# io-board-b-d.net
KiCad netlist of a schematic drawn in EAGLE
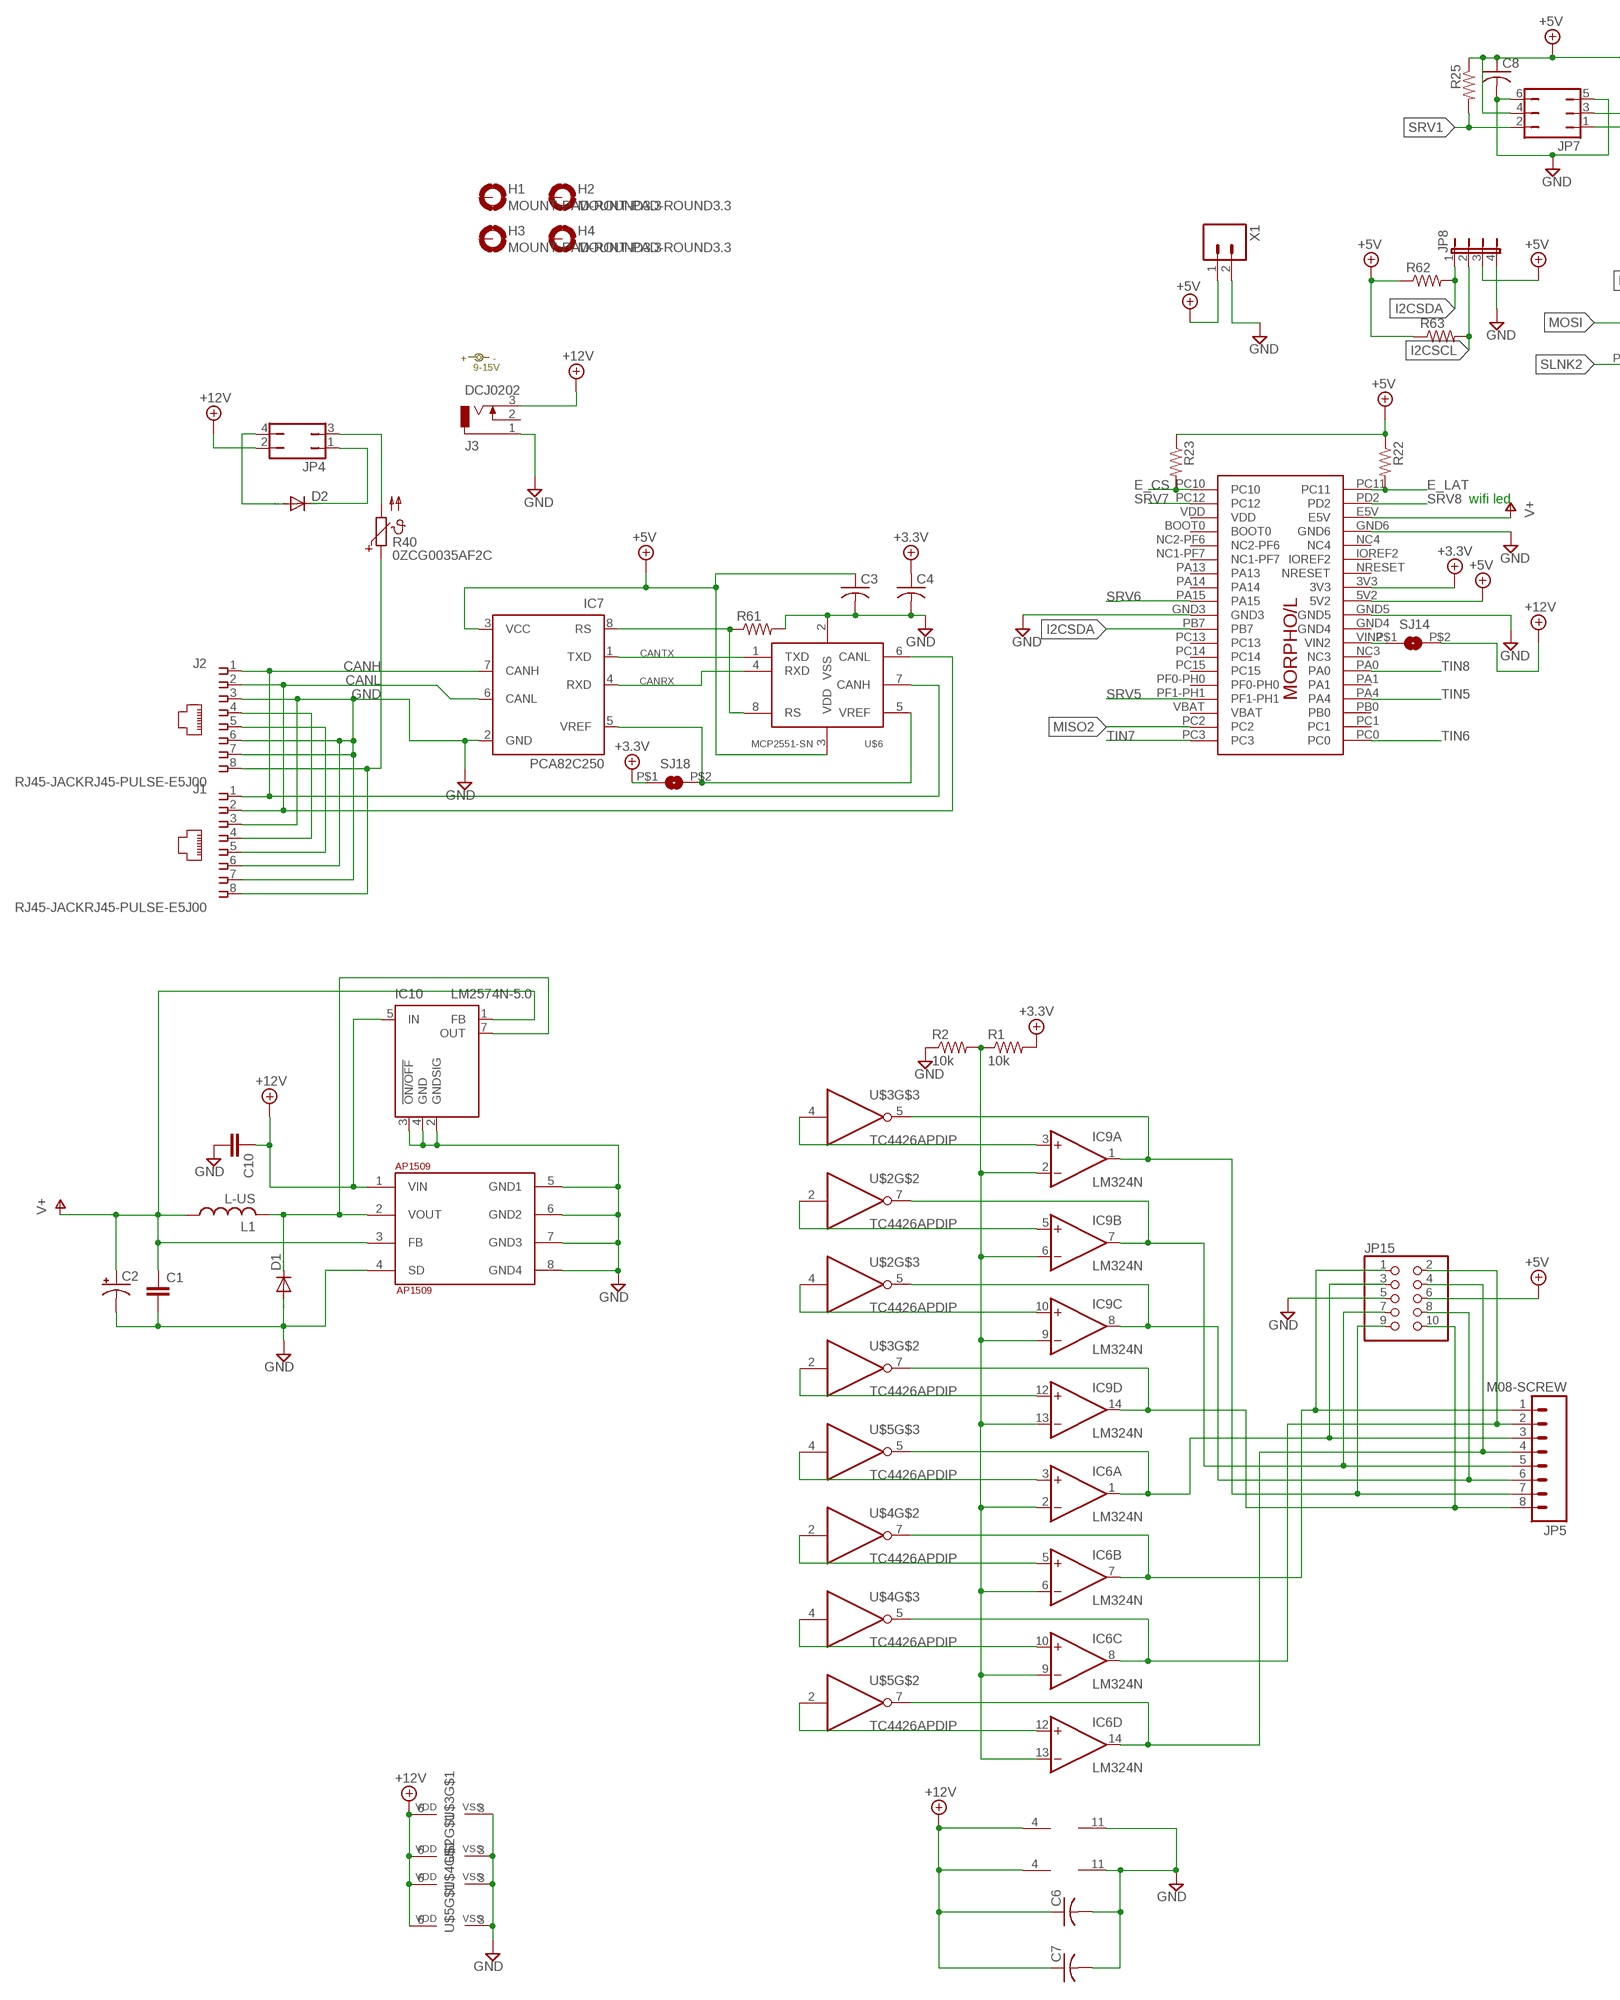
[diagram p0: schematic, sheet 1, part 1 of 2]
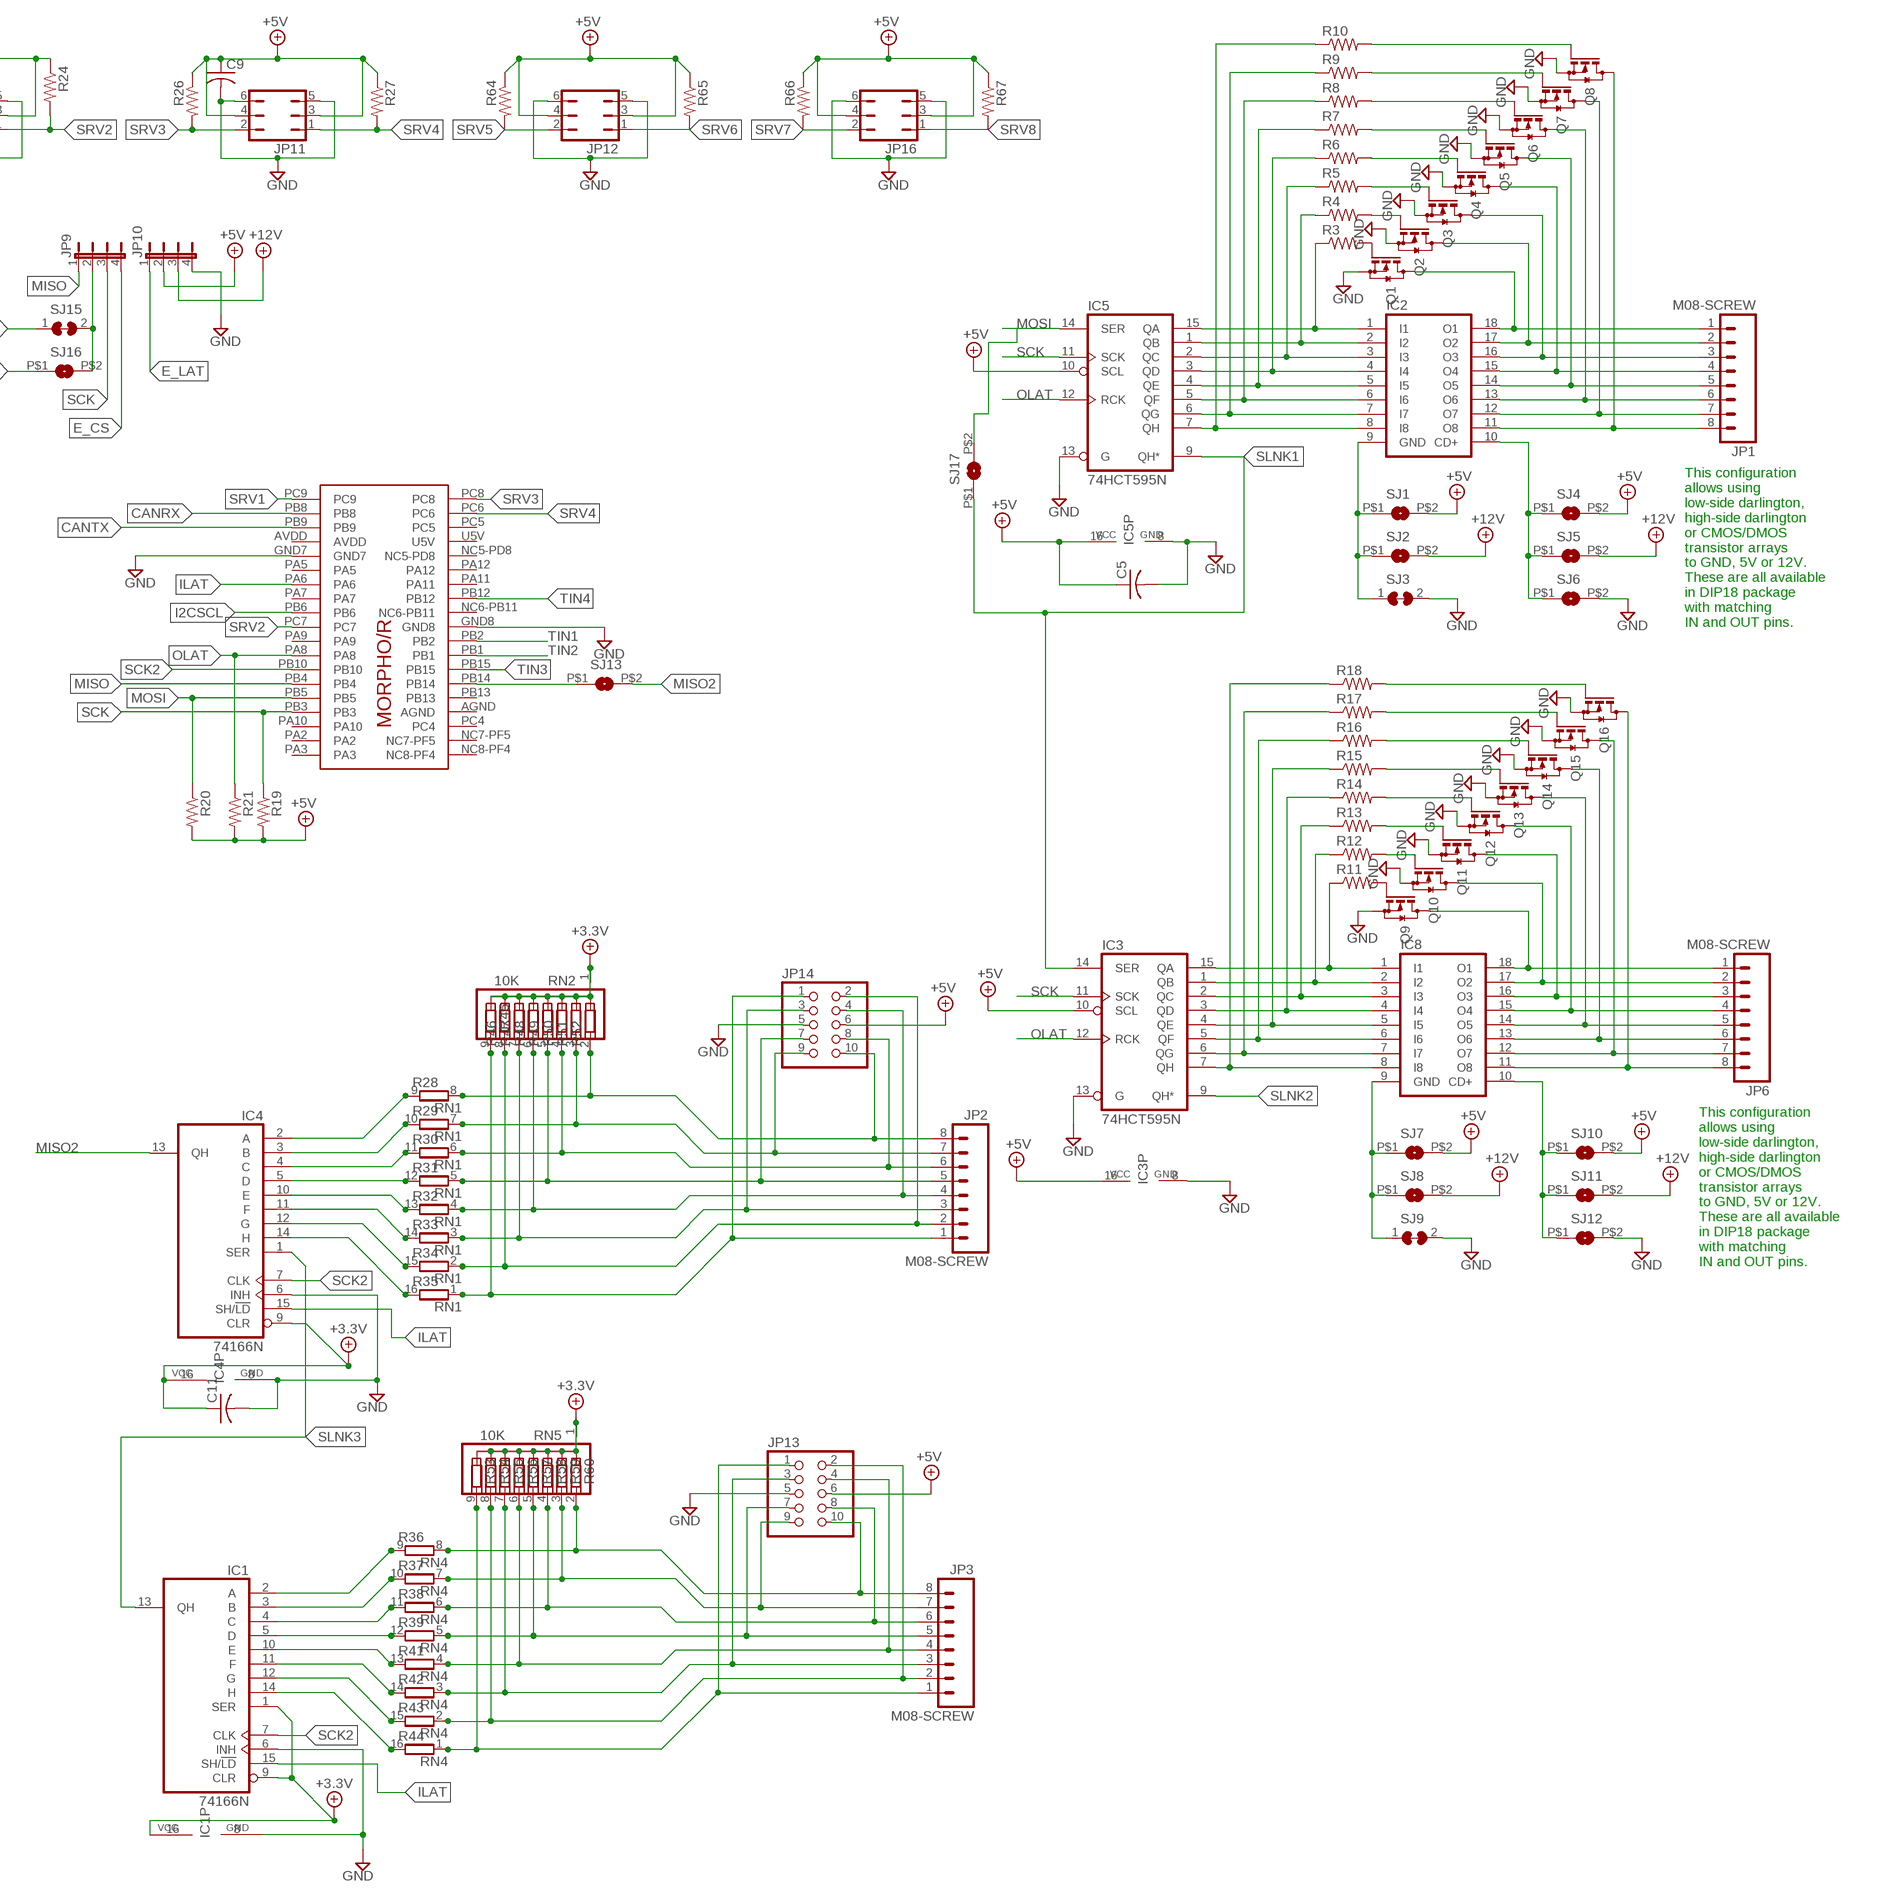
[diagram p1: schematic, sheet 1, part 2 of 2]

(export (version "E")
  (design (tool "Eeschema 10.0.6"))
  (components
    (comp (ref "+12V")
      (value "9-15V")
      (footprint "eagle-import:POWER_USAGE")
      (libsource (lib "eagle-import") (part "DOC-POWER_LABEL"))
    )
    (comp (ref "AP1509")
      (value "AP1509")
      (footprint "eagle-import:SO-08")
      (libsource (lib "eagle-import") (part "AP1509"))
    )
    (comp (ref "C1")
      (value "C-EUC1206")
      (footprint "eagle-import:C1206")
      (libsource (lib "eagle-import") (part "C-EUC1206"))
    )
    (comp (ref "C2")
      (value "CPOL-USE2.5-5")
      (footprint "eagle-import:E2,5-5")
      (libsource (lib "eagle-import") (part "CPOL-USE2.5-5"))
    )
    (comp (ref "C3")
      (value "C-USC0805")
      (footprint "eagle-import:C0805")
      (libsource (lib "eagle-import") (part "C-USC0805"))
    )
    (comp (ref "C4")
      (value "C-USC0805")
      (footprint "eagle-import:C0805")
      (libsource (lib "eagle-import") (part "C-USC0805"))
    )
    (comp (ref "C5")
      (value "C-USC0805")
      (footprint "eagle-import:C0805")
      (libsource (lib "eagle-import") (part "C-USC0805"))
    )
    (comp (ref "C6")
      (value "C-USC1206")
      (footprint "eagle-import:C1206")
      (libsource (lib "eagle-import") (part "C-USC1206"))
    )
    (comp (ref "C7")
      (value "C-USC1206")
      (footprint "eagle-import:C1206")
      (libsource (lib "eagle-import") (part "C-USC1206"))
    )
    (comp (ref "C8")
      (value "C-USC1206")
      (footprint "eagle-import:C1206")
      (libsource (lib "eagle-import") (part "C-USC1206"))
    )
    (comp (ref "C9")
      (value "C-USC1206")
      (footprint "eagle-import:C1206")
      (libsource (lib "eagle-import") (part "C-USC1206"))
    )
    (comp (ref "C10")
      (value "C-EUC1206")
      (footprint "eagle-import:C1206")
      (libsource (lib "eagle-import") (part "C-EUC1206"))
    )
    (comp (ref "C11")
      (value "C-USC0805")
      (footprint "eagle-import:C0805")
      (libsource (lib "eagle-import") (part "C-USC0805"))
    )
    (comp (ref "D1")
      (value "DIODE-DO41-7.6")
      (footprint "eagle-import:DO41-7.6")
      (libsource (lib "eagle-import") (part "DIODE-DO41-7.6"))
    )
    (comp (ref "D2")
      (value "DIODE-DO41-7.6")
      (footprint "eagle-import:DO41-7.6")
      (libsource (lib "eagle-import") (part "DIODE-DO41-7.6"))
    )
    (comp (ref "H1")
      (value "MOUNT-PAD-ROUND3.3")
      (footprint "eagle-import:3,3-PAD")
      (libsource (lib "eagle-import") (part "MOUNT-PAD-ROUND3.3"))
    )
    (comp (ref "H2")
      (value "MOUNT-PAD-ROUND3.3")
      (footprint "eagle-import:3,3-PAD")
      (libsource (lib "eagle-import") (part "MOUNT-PAD-ROUND3.3"))
    )
    (comp (ref "H3")
      (value "MOUNT-PAD-ROUND3.3")
      (footprint "eagle-import:3,3-PAD")
      (libsource (lib "eagle-import") (part "MOUNT-PAD-ROUND3.3"))
    )
    (comp (ref "H4")
      (value "MOUNT-PAD-ROUND3.3")
      (footprint "eagle-import:3,3-PAD")
      (libsource (lib "eagle-import") (part "MOUNT-PAD-ROUND3.3"))
    )
    (comp (ref "IC1")
      (value "74166N")
      (footprint "eagle-import:DIL16")
      (libsource (lib "eagle-import") (part "74166N"))
    )
    (comp (ref "IC2")
      (value "ULN2803A")
      (footprint "eagle-import:DIL18-THIN")
      (libsource (lib "eagle-import") (part "ULN2803A"))
    )
    (comp (ref "IC3")
      (value "74HCT595N")
      (footprint "eagle-import:DIL16")
      (libsource (lib "eagle-import") (part "74595NHCT"))
    )
    (comp (ref "IC4")
      (value "74166N")
      (footprint "eagle-import:DIL16")
      (libsource (lib "eagle-import") (part "74166N"))
    )
    (comp (ref "IC5")
      (value "74HCT595N")
      (footprint "eagle-import:DIL16")
      (libsource (lib "eagle-import") (part "74595NHCT"))
    )
    (comp (ref "IC6")
      (value "LM324N")
      (footprint "eagle-import:DIL14")
      (libsource (lib "eagle-import") (part "LM324N"))
    )
    (comp (ref "IC7")
      (value "PCA82C250")
      (footprint "eagle-import:DIL08")
      (libsource (lib "eagle-import") (part "PCA82C250"))
    )
    (comp (ref "IC8")
      (value "ULN2803A")
      (footprint "eagle-import:DIL18-THIN")
      (libsource (lib "eagle-import") (part "ULN2803A"))
    )
    (comp (ref "IC9")
      (value "LM324N")
      (footprint "eagle-import:DIL14")
      (libsource (lib "eagle-import") (part "LM324N"))
    )
    (comp (ref "IC10")
      (value "LM2574N-5.0")
      (footprint "eagle-import:DIL08")
      (libsource (lib "eagle-import") (part "LM2574?-N5.0"))
    )
    (comp (ref "J1")
      (value "RJ45-JACKRJ45-PULSE-E5J00")
      (footprint "eagle-import:RJ45-PULSE-E5J88")
      (libsource (lib "eagle-import") (part "RJ45-JACKRJ45-PULSE-E5J00"))
    )
    (comp (ref "J2")
      (value "RJ45-JACKRJ45-PULSE-E5J00")
      (footprint "eagle-import:RJ45-PULSE-E5J88")
      (libsource (lib "eagle-import") (part "RJ45-JACKRJ45-PULSE-E5J00"))
    )
    (comp (ref "J3")
      (value "DCJ0202")
      (footprint "eagle-import:DCJ0202")
      (libsource (lib "eagle-import") (part "DCJ0202"))
    )
    (comp (ref "JP1")
      (value "M08-SCREW")
      (footprint "eagle-import:1X08_TERMINAL")
      (libsource (lib "eagle-import") (part "M08-SCREW"))
    )
    (comp (ref "JP2")
      (value "M08-SCREW")
      (footprint "eagle-import:1X08_TERMINAL")
      (libsource (lib "eagle-import") (part "M08-SCREW"))
    )
    (comp (ref "JP3")
      (value "M08-SCREW")
      (footprint "eagle-import:1X08_TERMINAL")
      (libsource (lib "eagle-import") (part "M08-SCREW"))
    )
    (comp (ref "JP4")
      (value "JP2Q")
      (footprint "eagle-import:JP2Q")
      (libsource (lib "eagle-import") (part "JP2Q"))
    )
    (comp (ref "JP5")
      (value "M08-SCREW")
      (footprint "eagle-import:1X08_TERMINAL")
      (libsource (lib "eagle-import") (part "M08-SCREW"))
    )
    (comp (ref "JP6")
      (value "M08-SCREW")
      (footprint "eagle-import:1X08_TERMINAL")
      (libsource (lib "eagle-import") (part "M08-SCREW"))
    )
    (comp (ref "JP7")
      (value "JP3Q")
      (footprint "eagle-import:JP3Q")
      (libsource (lib "eagle-import") (part "JP3Q"))
    )
    (comp (ref "JP8")
      (value "JP4-FLAT")
      (footprint "eagle-import:JP4F")
      (libsource (lib "eagle-import") (part "JP4-FLAT"))
    )
    (comp (ref "JP9")
      (value "JP4-FLAT")
      (footprint "eagle-import:JP4F")
      (libsource (lib "eagle-import") (part "JP4-FLAT"))
    )
    (comp (ref "JP10")
      (value "JP4-FLAT")
      (footprint "eagle-import:JP4F")
      (libsource (lib "eagle-import") (part "JP4-FLAT"))
    )
    (comp (ref "JP11")
      (value "JP3Q")
      (footprint "eagle-import:JP3Q")
      (libsource (lib "eagle-import") (part "JP3Q"))
    )
    (comp (ref "JP12")
      (value "JP3Q")
      (footprint "eagle-import:JP3Q")
      (libsource (lib "eagle-import") (part "JP3Q"))
    )
    (comp (ref "JP13")
      (value "PINHD-2X5CN")
      (footprint "eagle-import:CON10M")
      (libsource (lib "eagle-import") (part "PINHD-2X5CN"))
    )
    (comp (ref "JP14")
      (value "PINHD-2X5CN")
      (footprint "eagle-import:CON10M")
      (libsource (lib "eagle-import") (part "PINHD-2X5CN"))
    )
    (comp (ref "JP15")
      (value "PINHD-2X5CN")
      (footprint "eagle-import:CON10M")
      (libsource (lib "eagle-import") (part "PINHD-2X5CN"))
    )
    (comp (ref "JP16")
      (value "JP3Q")
      (footprint "eagle-import:JP3Q")
      (libsource (lib "eagle-import") (part "JP3Q"))
    )
    (comp (ref "L1")
      (value "L-US")
      (footprint "eagle-import:L5-8,5")
      (libsource (lib "eagle-import") (part "L-US"))
    )
    (comp (ref "Q1")
      (value "BSS123")
      (footprint "eagle-import:SOT23")
      (libsource (lib "eagle-import") (part "BSS123"))
    )
    (comp (ref "Q2")
      (value "BSS123")
      (footprint "eagle-import:SOT23")
      (libsource (lib "eagle-import") (part "BSS123"))
    )
    (comp (ref "Q3")
      (value "BSS123")
      (footprint "eagle-import:SOT23")
      (libsource (lib "eagle-import") (part "BSS123"))
    )
    (comp (ref "Q4")
      (value "BSS123")
      (footprint "eagle-import:SOT23")
      (libsource (lib "eagle-import") (part "BSS123"))
    )
    (comp (ref "Q5")
      (value "BSS123")
      (footprint "eagle-import:SOT23")
      (libsource (lib "eagle-import") (part "BSS123"))
    )
    (comp (ref "Q6")
      (value "BSS123")
      (footprint "eagle-import:SOT23")
      (libsource (lib "eagle-import") (part "BSS123"))
    )
    (comp (ref "Q7")
      (value "BSS123")
      (footprint "eagle-import:SOT23")
      (libsource (lib "eagle-import") (part "BSS123"))
    )
    (comp (ref "Q8")
      (value "BSS123")
      (footprint "eagle-import:SOT23")
      (libsource (lib "eagle-import") (part "BSS123"))
    )
    (comp (ref "Q9")
      (value "BSS123")
      (footprint "eagle-import:SOT23")
      (libsource (lib "eagle-import") (part "BSS123"))
    )
    (comp (ref "Q10")
      (value "BSS123")
      (footprint "eagle-import:SOT23")
      (libsource (lib "eagle-import") (part "BSS123"))
    )
    (comp (ref "Q11")
      (value "BSS123")
      (footprint "eagle-import:SOT23")
      (libsource (lib "eagle-import") (part "BSS123"))
    )
    (comp (ref "Q12")
      (value "BSS123")
      (footprint "eagle-import:SOT23")
      (libsource (lib "eagle-import") (part "BSS123"))
    )
    (comp (ref "Q13")
      (value "BSS123")
      (footprint "eagle-import:SOT23")
      (libsource (lib "eagle-import") (part "BSS123"))
    )
    (comp (ref "Q14")
      (value "BSS123")
      (footprint "eagle-import:SOT23")
      (libsource (lib "eagle-import") (part "BSS123"))
    )
    (comp (ref "Q15")
      (value "BSS123")
      (footprint "eagle-import:SOT23")
      (libsource (lib "eagle-import") (part "BSS123"))
    )
    (comp (ref "Q16")
      (value "BSS123")
      (footprint "eagle-import:SOT23")
      (libsource (lib "eagle-import") (part "BSS123"))
    )
    (comp (ref "R1")
      (value "10k")
      (footprint "eagle-import:R0805")
      (libsource (lib "eagle-import") (part "R-US_R0805"))
    )
    (comp (ref "R2")
      (value "10k")
      (footprint "eagle-import:R0805")
      (libsource (lib "eagle-import") (part "R-US_R0805"))
    )
    (comp (ref "R3")
      (value "R-US_R0603")
      (footprint "eagle-import:R0603")
      (libsource (lib "eagle-import") (part "R-US_R0603"))
    )
    (comp (ref "R4")
      (value "R-US_R0603")
      (footprint "eagle-import:R0603")
      (libsource (lib "eagle-import") (part "R-US_R0603"))
    )
    (comp (ref "R5")
      (value "R-US_R0603")
      (footprint "eagle-import:R0603")
      (libsource (lib "eagle-import") (part "R-US_R0603"))
    )
    (comp (ref "R6")
      (value "R-US_R0603")
      (footprint "eagle-import:R0603")
      (libsource (lib "eagle-import") (part "R-US_R0603"))
    )
    (comp (ref "R7")
      (value "R-US_R0603")
      (footprint "eagle-import:R0603")
      (libsource (lib "eagle-import") (part "R-US_R0603"))
    )
    (comp (ref "R8")
      (value "R-US_R0603")
      (footprint "eagle-import:R0603")
      (libsource (lib "eagle-import") (part "R-US_R0603"))
    )
    (comp (ref "R9")
      (value "R-US_R0603")
      (footprint "eagle-import:R0603")
      (libsource (lib "eagle-import") (part "R-US_R0603"))
    )
    (comp (ref "R10")
      (value "R-US_R0603")
      (footprint "eagle-import:R0603")
      (libsource (lib "eagle-import") (part "R-US_R0603"))
    )
    (comp (ref "R11")
      (value "R-US_R0603")
      (footprint "eagle-import:R0603")
      (libsource (lib "eagle-import") (part "R-US_R0603"))
    )
    (comp (ref "R12")
      (value "R-US_R0603")
      (footprint "eagle-import:R0603")
      (libsource (lib "eagle-import") (part "R-US_R0603"))
    )
    (comp (ref "R13")
      (value "R-US_R0603")
      (footprint "eagle-import:R0603")
      (libsource (lib "eagle-import") (part "R-US_R0603"))
    )
    (comp (ref "R14")
      (value "R-US_R0603")
      (footprint "eagle-import:R0603")
      (libsource (lib "eagle-import") (part "R-US_R0603"))
    )
    (comp (ref "R15")
      (value "R-US_R0603")
      (footprint "eagle-import:R0603")
      (libsource (lib "eagle-import") (part "R-US_R0603"))
    )
    (comp (ref "R16")
      (value "R-US_R0603")
      (footprint "eagle-import:R0603")
      (libsource (lib "eagle-import") (part "R-US_R0603"))
    )
    (comp (ref "R17")
      (value "R-US_R0603")
      (footprint "eagle-import:R0603")
      (libsource (lib "eagle-import") (part "R-US_R0603"))
    )
    (comp (ref "R18")
      (value "R-US_R0603")
      (footprint "eagle-import:R0603")
      (libsource (lib "eagle-import") (part "R-US_R0603"))
    )
    (comp (ref "R19")
      (value "R-US_R0805")
      (footprint "eagle-import:R0805")
      (libsource (lib "eagle-import") (part "rcl_334_R-US_R0805"))
    )
    (comp (ref "R20")
      (value "R-US_R0805")
      (footprint "eagle-import:R0805")
      (libsource (lib "eagle-import") (part "rcl_334_R-US_R0805"))
    )
    (comp (ref "R21")
      (value "R-US_R0805")
      (footprint "eagle-import:R0805")
      (libsource (lib "eagle-import") (part "rcl_334_R-US_R0805"))
    )
    (comp (ref "R22")
      (value "R-US_R0805")
      (footprint "eagle-import:R0805")
      (libsource (lib "eagle-import") (part "rcl_334_R-US_R0805"))
    )
    (comp (ref "R23")
      (value "R-US_R0805")
      (footprint "eagle-import:R0805")
      (libsource (lib "eagle-import") (part "rcl_334_R-US_R0805"))
    )
    (comp (ref "R24")
      (value "R-US_R0805")
      (footprint "eagle-import:R0805")
      (libsource (lib "eagle-import") (part "rcl_334_R-US_R0805"))
    )
    (comp (ref "R25")
      (value "R-US_R0805")
      (footprint "eagle-import:R0805")
      (libsource (lib "eagle-import") (part "rcl_334_R-US_R0805"))
    )
    (comp (ref "R26")
      (value "R-US_R0805")
      (footprint "eagle-import:R0805")
      (libsource (lib "eagle-import") (part "rcl_334_R-US_R0805"))
    )
    (comp (ref "R27")
      (value "R-US_R0805")
      (footprint "eagle-import:R0805")
      (libsource (lib "eagle-import") (part "rcl_334_R-US_R0805"))
    )
    (comp (ref "R28")
      (value "R-EU_R0603")
      (footprint "eagle-import:R0603")
      (libsource (lib "eagle-import") (part "R-EU_R0603"))
    )
    (comp (ref "R29")
      (value "R-EU_R0603")
      (footprint "eagle-import:R0603")
      (libsource (lib "eagle-import") (part "R-EU_R0603"))
    )
    (comp (ref "R30")
      (value "R-EU_R0603")
      (footprint "eagle-import:R0603")
      (libsource (lib "eagle-import") (part "R-EU_R0603"))
    )
    (comp (ref "R31")
      (value "R-EU_R0603")
      (footprint "eagle-import:R0603")
      (libsource (lib "eagle-import") (part "R-EU_R0603"))
    )
    (comp (ref "R32")
      (value "R-EU_R0603")
      (footprint "eagle-import:R0603")
      (libsource (lib "eagle-import") (part "R-EU_R0603"))
    )
    (comp (ref "R33")
      (value "R-EU_R0603")
      (footprint "eagle-import:R0603")
      (libsource (lib "eagle-import") (part "R-EU_R0603"))
    )
    (comp (ref "R34")
      (value "R-EU_R0603")
      (footprint "eagle-import:R0603")
      (libsource (lib "eagle-import") (part "R-EU_R0603"))
    )
    (comp (ref "R35")
      (value "R-EU_R0603")
      (footprint "eagle-import:R0603")
      (libsource (lib "eagle-import") (part "R-EU_R0603"))
    )
    (comp (ref "R36")
      (value "R-EU_R0603")
      (footprint "eagle-import:R0603")
      (libsource (lib "eagle-import") (part "R-EU_R0603"))
    )
    (comp (ref "R37")
      (value "R-EU_R0603")
      (footprint "eagle-import:R0603")
      (libsource (lib "eagle-import") (part "R-EU_R0603"))
    )
    (comp (ref "R38")
      (value "R-EU_R0603")
      (footprint "eagle-import:R0603")
      (libsource (lib "eagle-import") (part "R-EU_R0603"))
    )
    (comp (ref "R39")
      (value "R-EU_R0603")
      (footprint "eagle-import:R0603")
      (libsource (lib "eagle-import") (part "R-EU_R0603"))
    )
    (comp (ref "R40")
      (value "0ZCG0035AF2C")
      (footprint "eagle-import:PTC1812")
      (libsource (lib "eagle-import") (part "PTC_1812"))
    )
    (comp (ref "R41")
      (value "R-EU_R0603")
      (footprint "eagle-import:R0603")
      (libsource (lib "eagle-import") (part "R-EU_R0603"))
    )
    (comp (ref "R42")
      (value "R-EU_R0603")
      (footprint "eagle-import:R0603")
      (libsource (lib "eagle-import") (part "R-EU_R0603"))
    )
    (comp (ref "R43")
      (value "R-EU_R0603")
      (footprint "eagle-import:R0603")
      (libsource (lib "eagle-import") (part "R-EU_R0603"))
    )
    (comp (ref "R44")
      (value "R-EU_R0603")
      (footprint "eagle-import:R0603")
      (libsource (lib "eagle-import") (part "R-EU_R0603"))
    )
    (comp (ref "R45")
      (value "R-EU_R0603")
      (footprint "eagle-import:R0603")
      (libsource (lib "eagle-import") (part "R-EU_R0603"))
    )
    (comp (ref "R46")
      (value "R-EU_R0603")
      (footprint "eagle-import:R0603")
      (libsource (lib "eagle-import") (part "R-EU_R0603"))
    )
    (comp (ref "R47")
      (value "R-EU_R0603")
      (footprint "eagle-import:R0603")
      (libsource (lib "eagle-import") (part "R-EU_R0603"))
    )
    (comp (ref "R48")
      (value "R-EU_R0603")
      (footprint "eagle-import:R0603")
      (libsource (lib "eagle-import") (part "R-EU_R0603"))
    )
    (comp (ref "R49")
      (value "R-EU_R0603")
      (footprint "eagle-import:R0603")
      (libsource (lib "eagle-import") (part "R-EU_R0603"))
    )
    (comp (ref "R50")
      (value "R-EU_R0603")
      (footprint "eagle-import:R0603")
      (libsource (lib "eagle-import") (part "R-EU_R0603"))
    )
    (comp (ref "R51")
      (value "R-EU_R0603")
      (footprint "eagle-import:R0603")
      (libsource (lib "eagle-import") (part "R-EU_R0603"))
    )
    (comp (ref "R52")
      (value "R-EU_R0603")
      (footprint "eagle-import:R0603")
      (libsource (lib "eagle-import") (part "R-EU_R0603"))
    )
    (comp (ref "R53")
      (value "R-EU_R0603")
      (footprint "eagle-import:R0603")
      (libsource (lib "eagle-import") (part "R-EU_R0603"))
    )
    (comp (ref "R54")
      (value "R-EU_R0603")
      (footprint "eagle-import:R0603")
      (libsource (lib "eagle-import") (part "R-EU_R0603"))
    )
    (comp (ref "R55")
      (value "R-EU_R0603")
      (footprint "eagle-import:R0603")
      (libsource (lib "eagle-import") (part "R-EU_R0603"))
    )
    (comp (ref "R56")
      (value "R-EU_R0603")
      (footprint "eagle-import:R0603")
      (libsource (lib "eagle-import") (part "R-EU_R0603"))
    )
    (comp (ref "R57")
      (value "R-EU_R0603")
      (footprint "eagle-import:R0603")
      (libsource (lib "eagle-import") (part "R-EU_R0603"))
    )
    (comp (ref "R58")
      (value "R-EU_R0603")
      (footprint "eagle-import:R0603")
      (libsource (lib "eagle-import") (part "R-EU_R0603"))
    )
    (comp (ref "R59")
      (value "R-EU_R0603")
      (footprint "eagle-import:R0603")
      (libsource (lib "eagle-import") (part "R-EU_R0603"))
    )
    (comp (ref "R60")
      (value "R-EU_R0603")
      (footprint "eagle-import:R0603")
      (libsource (lib "eagle-import") (part "R-EU_R0603"))
    )
    (comp (ref "R61")
      (value "R-US_R0805")
      (footprint "eagle-import:R0805")
      (libsource (lib "eagle-import") (part "rcl_334_R-US_R0805"))
    )
    (comp (ref "R62")
      (value "R-US_R0805")
      (footprint "eagle-import:R0805")
      (libsource (lib "eagle-import") (part "rcl_334_R-US_R0805"))
    )
    (comp (ref "R63")
      (value "R-US_R0805")
      (footprint "eagle-import:R0805")
      (libsource (lib "eagle-import") (part "rcl_334_R-US_R0805"))
    )
    (comp (ref "R64")
      (value "R-US_R0805")
      (footprint "eagle-import:R0805")
      (libsource (lib "eagle-import") (part "rcl_334_R-US_R0805"))
    )
    (comp (ref "R65")
      (value "R-US_R0805")
      (footprint "eagle-import:R0805")
      (libsource (lib "eagle-import") (part "rcl_334_R-US_R0805"))
    )
    (comp (ref "R66")
      (value "R-US_R0805")
      (footprint "eagle-import:R0805")
      (libsource (lib "eagle-import") (part "rcl_334_R-US_R0805"))
    )
    (comp (ref "R67")
      (value "R-US_R0805")
      (footprint "eagle-import:R0805")
      (libsource (lib "eagle-import") (part "rcl_334_R-US_R0805"))
    )
    (comp (ref "RN1")
      (value "8R-P")
      (footprint "eagle-import:DIL16")
      (libsource (lib "eagle-import") (part "8R-P"))
    )
    (comp (ref "RN2")
      (value "10K")
      (footprint "eagle-import:SIL9")
      (libsource (lib "eagle-import") (part "G08R"))
    )
    (comp (ref "RN4")
      (value "8R-P")
      (footprint "eagle-import:DIL16")
      (libsource (lib "eagle-import") (part "8R-P"))
    )
    (comp (ref "RN5")
      (value "10K")
      (footprint "eagle-import:SIL9")
      (libsource (lib "eagle-import") (part "G08R"))
    )
    (comp (ref "SJ1")
      (value "SJRND2")
      (footprint "eagle-import:SJ_RND2")
      (libsource (lib "eagle-import") (part "SJRND2"))
    )
    (comp (ref "SJ2")
      (value "SJRND2")
      (footprint "eagle-import:SJ_RND2")
      (libsource (lib "eagle-import") (part "SJRND2"))
    )
    (comp (ref "SJ3")
      (value "SJ-C")
      (footprint "eagle-import:SJW-C")
      (libsource (lib "eagle-import") (part "SJ-C"))
    )
    (comp (ref "SJ4")
      (value "SJRND2")
      (footprint "eagle-import:SJ_RND2")
      (libsource (lib "eagle-import") (part "SJRND2"))
    )
    (comp (ref "SJ5")
      (value "SJRND2")
      (footprint "eagle-import:SJ_RND2")
      (libsource (lib "eagle-import") (part "SJRND2"))
    )
    (comp (ref "SJ6")
      (value "SJRND2")
      (footprint "eagle-import:SJ_RND2")
      (libsource (lib "eagle-import") (part "SJRND2"))
    )
    (comp (ref "SJ7")
      (value "SJRND2")
      (footprint "eagle-import:SJ_RND2")
      (libsource (lib "eagle-import") (part "SJRND2"))
    )
    (comp (ref "SJ8")
      (value "SJRND2")
      (footprint "eagle-import:SJ_RND2")
      (libsource (lib "eagle-import") (part "SJRND2"))
    )
    (comp (ref "SJ9")
      (value "SJ-C")
      (footprint "eagle-import:SJW-C")
      (libsource (lib "eagle-import") (part "SJ-C"))
    )
    (comp (ref "SJ10")
      (value "SJRND2")
      (footprint "eagle-import:SJ_RND2")
      (libsource (lib "eagle-import") (part "SJRND2"))
    )
    (comp (ref "SJ11")
      (value "SJRND2")
      (footprint "eagle-import:SJ_RND2")
      (libsource (lib "eagle-import") (part "SJRND2"))
    )
    (comp (ref "SJ12")
      (value "SJRND2")
      (footprint "eagle-import:SJ_RND2")
      (libsource (lib "eagle-import") (part "SJRND2"))
    )
    (comp (ref "SJ13")
      (value "SJRND2")
      (footprint "eagle-import:SJ_RND2")
      (libsource (lib "eagle-import") (part "SJRND2"))
    )
    (comp (ref "SJ14")
      (value "SJRND2")
      (footprint "eagle-import:SJ_RND2")
      (libsource (lib "eagle-import") (part "SJRND2"))
    )
    (comp (ref "SJ15")
      (value "SJ-C")
      (footprint "eagle-import:SJW-C")
      (libsource (lib "eagle-import") (part "SJ-C"))
    )
    (comp (ref "SJ16")
      (value "SJRND2")
      (footprint "eagle-import:SJ_RND2")
      (libsource (lib "eagle-import") (part "SJRND2"))
    )
    (comp (ref "SJ17")
      (value "SJRND2")
      (footprint "eagle-import:SJ_RND2")
      (libsource (lib "eagle-import") (part "SJRND2"))
    )
    (comp (ref "SJ18")
      (value "SJRND2")
      (footprint "eagle-import:SJ_RND2")
      (libsource (lib "eagle-import") (part "SJRND2"))
    )
    (comp (ref "U$1")
      (value "NUCLEO_64_GENERIC")
      (footprint "eagle-import:NUCLEO_BRD_BASE64")
      (libsource (lib "eagle-import") (part "NUCLEO_64_GENERIC"))
    )
    (comp (ref "U$2")
      (value "TC4426APDIP")
      (footprint "eagle-import:DIL08-LONG")
      (libsource (lib "eagle-import") (part "TC4426APDIP"))
    )
    (comp (ref "U$3")
      (value "TC4426APDIP")
      (footprint "eagle-import:DIL08-LONG")
      (libsource (lib "eagle-import") (part "TC4426APDIP"))
    )
    (comp (ref "U$4")
      (value "TC4426APDIP")
      (footprint "eagle-import:DIL08-LONG")
      (libsource (lib "eagle-import") (part "TC4426APDIP"))
    )
    (comp (ref "U$5")
      (value "TC4426APDIP")
      (footprint "eagle-import:DIL08-LONG")
      (libsource (lib "eagle-import") (part "TC4426APDIP"))
    )
    (comp (ref "U$6")
      (value "MCP2551-SN")
      (footprint "eagle-import:SO-08")
      (libsource (lib "eagle-import") (part "MCP2551-SN"))
    )
    (comp (ref "X1")
      (value "CONNECTOR-M023.5MM-LOCK")
      (footprint "eagle-import:SCREWTERMINAL-3.5MM-2_LOCK")
      (libsource (lib "eagle-import") (part "CONNECTOR-M023.5MM-LOCK"))
    )
  )
  (nets
    (net (code "1") (name "+3.3V") (class "Default")
      (node (ref "C11") (pin "1") (pinfunction "1_1") (pintype "passive"))
      (node (ref "C4") (pin "1") (pinfunction "1_1") (pintype "passive"))
      (node (ref "IC1") (pin "1") (pinfunction "SER_1") (pintype "input"))
      (node (ref "IC1") (pin "16") (pinfunction "VCC_16") (pintype "power_in"))
      (node (ref "IC1") (pin "9") (pinfunction "CLR_9") (pintype "input"))
      (node (ref "IC4") (pin "16") (pinfunction "VCC_16") (pintype "power_in"))
      (node (ref "IC4") (pin "9") (pinfunction "CLR_9") (pintype "input"))
      (node (ref "R1") (pin "2") (pinfunction "2_2") (pintype "passive"))
      (node (ref "R45") (pin "1") (pinfunction "1_1") (pintype "passive"))
      (node (ref "R46") (pin "2") (pinfunction "2_2") (pintype "passive"))
      (node (ref "R47") (pin "2") (pinfunction "2_2") (pintype "passive"))
      (node (ref "R48") (pin "2") (pinfunction "2_2") (pintype "passive"))
      (node (ref "R49") (pin "2") (pinfunction "2_2") (pintype "passive"))
      (node (ref "R50") (pin "2") (pinfunction "2_2") (pintype "passive"))
      (node (ref "R51") (pin "2") (pinfunction "2_2") (pintype "passive"))
      (node (ref "R52") (pin "2") (pinfunction "2_2") (pintype "passive"))
      (node (ref "R53") (pin "1") (pinfunction "1_1") (pintype "passive"))
      (node (ref "R54") (pin "1") (pinfunction "1_1") (pintype "passive"))
      (node (ref "R55") (pin "1") (pinfunction "1_1") (pintype "passive"))
      (node (ref "R56") (pin "1") (pinfunction "1_1") (pintype "passive"))
      (node (ref "R57") (pin "1") (pinfunction "1_1") (pintype "passive"))
      (node (ref "R58") (pin "1") (pinfunction "1_1") (pintype "passive"))
      (node (ref "R59") (pin "1") (pinfunction "1_1") (pintype "passive"))
      (node (ref "R60") (pin "1") (pinfunction "1_1") (pintype "passive"))
      (node (ref "RN2") (pin "1") (pinfunction "1_1") (pintype "passive"))
      (node (ref "RN5") (pin "1") (pinfunction "1_1") (pintype "passive"))
      (node (ref "SJ18") (pin "P$1") (pinfunction "1_P$1") (pintype "passive"))
      (node (ref "U$1") (pin "3V3") (pinfunction "3V3_3V3") (pintype "power_in"))
    )
    (net (code "2") (name "+5V") (class "Default")
      (node (ref "C3") (pin "1") (pinfunction "1_1") (pintype "passive"))
      (node (ref "C5") (pin "1") (pinfunction "1_1") (pintype "passive"))
      (node (ref "C8") (pin "1") (pinfunction "1_1") (pintype "passive"))
      (node (ref "C9") (pin "1") (pinfunction "1_1") (pintype "passive"))
      (node (ref "IC3") (pin "10") (pinfunction "SCL_10") (pintype "input"))
      (node (ref "IC3") (pin "16") (pinfunction "VCC_16") (pintype "power_in"))
      (node (ref "IC5") (pin "10") (pinfunction "SCL_10") (pintype "input"))
      (node (ref "IC5") (pin "16") (pinfunction "VCC_16") (pintype "power_in"))
      (node (ref "IC7") (pin "3") (pinfunction "VCC_3") (pintype "power_in"))
      (node (ref "JP10") (pin "2") (pinfunction "2_2") (pintype "passive"))
      (node (ref "JP11") (pin "3") (pinfunction "3_3") (pintype "passive"))
      (node (ref "JP11") (pin "4") (pinfunction "4_4") (pintype "passive"))
      (node (ref "JP12") (pin "3") (pinfunction "3_3") (pintype "passive"))
      (node (ref "JP12") (pin "4") (pinfunction "4_4") (pintype "passive"))
      (node (ref "JP13") (pin "6") (pinfunction "6_6") (pintype "passive"))
      (node (ref "JP14") (pin "6") (pinfunction "6_6") (pintype "passive"))
      (node (ref "JP15") (pin "6") (pinfunction "6_6") (pintype "passive"))
      (node (ref "JP16") (pin "3") (pinfunction "3_3") (pintype "passive"))
      (node (ref "JP16") (pin "4") (pinfunction "4_4") (pintype "passive"))
      (node (ref "JP7") (pin "3") (pinfunction "3_3") (pintype "passive"))
      (node (ref "JP7") (pin "4") (pinfunction "4_4") (pintype "passive"))
      (node (ref "JP8") (pin "3") (pinfunction "3_3") (pintype "passive"))
      (node (ref "R19") (pin "2") (pinfunction "2_2") (pintype "passive"))
      (node (ref "R20") (pin "2") (pinfunction "2_2") (pintype "passive"))
      (node (ref "R21") (pin "2") (pinfunction "2_2") (pintype "passive"))
      (node (ref "R22") (pin "1") (pinfunction "1_1") (pintype "passive"))
      (node (ref "R23") (pin "1") (pinfunction "1_1") (pintype "passive"))
      (node (ref "R24") (pin "1") (pinfunction "1_1") (pintype "passive"))
      (node (ref "R25") (pin "1") (pinfunction "1_1") (pintype "passive"))
      (node (ref "R26") (pin "1") (pinfunction "1_1") (pintype "passive"))
      (node (ref "R27") (pin "1") (pinfunction "1_1") (pintype "passive"))
      (node (ref "R62") (pin "1") (pinfunction "1_1") (pintype "passive"))
      (node (ref "R63") (pin "1") (pinfunction "1_1") (pintype "passive"))
      (node (ref "R64") (pin "1") (pinfunction "1_1") (pintype "passive"))
      (node (ref "R65") (pin "1") (pinfunction "1_1") (pintype "passive"))
      (node (ref "R66") (pin "1") (pinfunction "1_1") (pintype "passive"))
      (node (ref "R67") (pin "1") (pinfunction "1_1") (pintype "passive"))
      (node (ref "SJ1") (pin "P$2") (pinfunction "2_P$2") (pintype "passive"))
      (node (ref "SJ10") (pin "P$2") (pinfunction "2_P$2") (pintype "passive"))
      (node (ref "SJ4") (pin "P$2") (pinfunction "2_P$2") (pintype "passive"))
      (node (ref "SJ7") (pin "P$2") (pinfunction "2_P$2") (pintype "passive"))
      (node (ref "U$1") (pin "5V2") (pinfunction "5V2_5V2") (pintype "power_in"))
      (node (ref "U$6") (pin "3") (pinfunction "VDD_3") (pintype "power_in"))
      (node (ref "X1") (pin "1") (pinfunction "1_1") (pintype "passive"))
    )
    (net (code "3") (name "+12V") (class "Default")
      (node (ref "AP1509") (pin "1") (pinfunction "VIN_1") (pintype "bidirectional"))
      (node (ref "C10") (pin "1") (pinfunction "1_1") (pintype "passive"))
      (node (ref "C6") (pin "1") (pinfunction "1_1") (pintype "passive"))
      (node (ref "C7") (pin "1") (pinfunction "1_1") (pintype "passive"))
      (node (ref "IC10") (pin "5") (pinfunction "IN_5") (pintype "input"))
      (node (ref "IC6") (pin "4") (pinfunction "V+_4") (pintype "power_in"))
      (node (ref "IC9") (pin "4") (pinfunction "V+_4") (pintype "power_in"))
      (node (ref "J3") (pin "3") (pinfunction "3_3") (pintype "passive"))
      (node (ref "JP10") (pin "3") (pinfunction "3_3") (pintype "passive"))
      (node (ref "JP4") (pin "2") (pinfunction "2_2") (pintype "passive"))
      (node (ref "SJ11") (pin "P$2") (pinfunction "2_P$2") (pintype "passive"))
      (node (ref "SJ14") (pin "P$2") (pinfunction "2_P$2") (pintype "passive"))
      (node (ref "SJ2") (pin "P$2") (pinfunction "2_P$2") (pintype "passive"))
      (node (ref "SJ5") (pin "P$2") (pinfunction "2_P$2") (pintype "passive"))
      (node (ref "SJ8") (pin "P$2") (pinfunction "2_P$2") (pintype "passive"))
      (node (ref "U$2") (pin "6") (pinfunction "VDD_6") (pintype "power_in"))
      (node (ref "U$3") (pin "6") (pinfunction "VDD_6") (pintype "power_in"))
      (node (ref "U$4") (pin "6") (pinfunction "VDD_6") (pintype "power_in"))
      (node (ref "U$5") (pin "6") (pinfunction "VDD_6") (pintype "power_in"))
    )
    (net (code "4") (name "/AGND") (class "Default")
      (node (ref "U$1") (pin "AGND") (pinfunction "AGND_AGND") (pintype "power_in"))
    )
    (net (code "5") (name "/AVDD") (class "Default")
      (node (ref "U$1") (pin "AVDD") (pinfunction "AVDD_AVDD") (pintype "power_in"))
    )
    (net (code "6") (name "/CANH") (class "Default")
      (node (ref "IC7") (pin "7") (pinfunction "CANH_7") (pintype "bidirectional"))
      (node (ref "J1") (pin "1") (pinfunction "1_1") (pintype "passive"))
      (node (ref "J2") (pin "1") (pinfunction "1_1") (pintype "passive"))
      (node (ref "U$6") (pin "7") (pinfunction "CANH_7") (pintype "bidirectional"))
    )
    (net (code "7") (name "/CANL") (class "Default")
      (node (ref "IC7") (pin "6") (pinfunction "CANL_6") (pintype "bidirectional"))
      (node (ref "J1") (pin "2") (pinfunction "2_2") (pintype "passive"))
      (node (ref "J2") (pin "2") (pinfunction "2_2") (pintype "passive"))
      (node (ref "U$6") (pin "6") (pinfunction "CANL_6") (pintype "bidirectional"))
    )
    (net (code "8") (name "/GND4") (class "Default")
      (node (ref "U$1") (pin "GND4") (pinfunction "GND4_GND4") (pintype "power_in"))
    )
    (net (code "9") (name "/TIN1") (class "Default")
      (node (ref "IC9") (pin "3") (pinfunction "+IN_3") (pintype "input"))
      (node (ref "U$1") (pin "PB2") (pinfunction "PB2_PB2") (pintype "bidirectional"))
      (node (ref "U$3") (pin "4") (pinfunction "I_4") (pintype "input"))
    )
    (net (code "10") (name "/TIN2") (class "Default")
      (node (ref "IC9") (pin "5") (pinfunction "+IN_5") (pintype "input"))
      (node (ref "U$1") (pin "PB1") (pinfunction "PB1_PB1") (pintype "bidirectional"))
      (node (ref "U$2") (pin "2") (pinfunction "I_2") (pintype "input"))
    )
    (net (code "11") (name "/TIN5") (class "Default")
      (node (ref "IC6") (pin "3") (pinfunction "+IN_3") (pintype "input"))
      (node (ref "U$1") (pin "PA4") (pinfunction "PA4_PA4") (pintype "bidirectional"))
      (node (ref "U$5") (pin "4") (pinfunction "I_4") (pintype "input"))
    )
    (net (code "12") (name "/TIN6") (class "Default")
      (node (ref "IC6") (pin "5") (pinfunction "+IN_5") (pintype "input"))
      (node (ref "U$1") (pin "PC0") (pinfunction "PC0_PC0") (pintype "bidirectional"))
      (node (ref "U$4") (pin "2") (pinfunction "I_2") (pintype "input"))
    )
    (net (code "13") (name "/TIN7") (class "Default")
      (node (ref "IC6") (pin "10") (pinfunction "+IN_10") (pintype "input"))
      (node (ref "U$1") (pin "PC3") (pinfunction "PC3_PC3") (pintype "bidirectional"))
      (node (ref "U$4") (pin "4") (pinfunction "I_4") (pintype "input"))
    )
    (net (code "14") (name "/TIN8") (class "Default")
      (node (ref "IC6") (pin "12") (pinfunction "+IN_12") (pintype "input"))
      (node (ref "U$1") (pin "PA0") (pinfunction "PA0_PA0") (pintype "bidirectional"))
      (node (ref "U$5") (pin "2") (pinfunction "I_2") (pintype "input"))
    )
    (net (code "15") (name "/U5V") (class "Default")
      (node (ref "U$1") (pin "U5V") (pinfunction "U5V_U5V") (pintype "power_in"))
    )
    (net (code "16") (name "/VBAT") (class "Default")
      (node (ref "U$1") (pin "VBAT") (pinfunction "VBAT_VBAT") (pintype "power_in"))
    )
    (net (code "17") (name "/VDD") (class "Default")
      (node (ref "U$1") (pin "VDD") (pinfunction "VDD_VDD") (pintype "power_in"))
    )
    (net (code "18") (name "CANRX") (class "Default")
      (node (ref "IC7") (pin "4") (pinfunction "RXD_4") (pintype "output"))
      (node (ref "U$1") (pin "PB8") (pinfunction "PB8_PB8") (pintype "bidirectional"))
      (node (ref "U$6") (pin "4") (pinfunction "RXD_4") (pintype "bidirectional"))
    )
    (net (code "19") (name "CANTX") (class "Default")
      (node (ref "IC7") (pin "1") (pinfunction "TXD_1") (pintype "input"))
      (node (ref "U$1") (pin "PB9") (pinfunction "PB9_PB9") (pintype "bidirectional"))
      (node (ref "U$6") (pin "1") (pinfunction "TXD_1") (pintype "bidirectional"))
    )
    (net (code "20") (name "E_CS") (class "Default")
      (node (ref "JP9") (pin "4") (pinfunction "4_4") (pintype "passive"))
      (node (ref "R23") (pin "2") (pinfunction "2_2") (pintype "passive"))
      (node (ref "U$1") (pin "PC10") (pinfunction "PC10_PC10") (pintype "bidirectional"))
    )
    (net (code "21") (name "E_LAT") (class "Default")
      (node (ref "JP10") (pin "1") (pinfunction "1_1") (pintype "passive"))
      (node (ref "R22") (pin "2") (pinfunction "2_2") (pintype "passive"))
      (node (ref "U$1") (pin "PC11") (pinfunction "PC11_PC11") (pintype "bidirectional"))
    )
    (net (code "22") (name "GND") (class "Default")
      (node (ref "AP1509") (pin "4") (pinfunction "SD_4") (pintype "bidirectional"))
      (node (ref "AP1509") (pin "5") (pinfunction "GND1_5") (pintype "power_in"))
      (node (ref "AP1509") (pin "6") (pinfunction "GND2_6") (pintype "power_in"))
      (node (ref "AP1509") (pin "7") (pinfunction "GND3_7") (pintype "power_in"))
      (node (ref "AP1509") (pin "8") (pinfunction "GND4_8") (pintype "power_in"))
      (node (ref "C1") (pin "2") (pinfunction "2_2") (pintype "passive"))
      (node (ref "C10") (pin "2") (pinfunction "2_2") (pintype "passive"))
      (node (ref "C11") (pin "2") (pinfunction "2_2") (pintype "passive"))
      (node (ref "C2") (pin "-") (pinfunction "-_-") (pintype "passive"))
      (node (ref "C3") (pin "2") (pinfunction "2_2") (pintype "passive"))
      (node (ref "C4") (pin "2") (pinfunction "2_2") (pintype "passive"))
      (node (ref "C5") (pin "2") (pinfunction "2_2") (pintype "passive"))
      (node (ref "C6") (pin "2") (pinfunction "2_2") (pintype "passive"))
      (node (ref "C7") (pin "2") (pinfunction "2_2") (pintype "passive"))
      (node (ref "C8") (pin "2") (pinfunction "2_2") (pintype "passive"))
      (node (ref "C9") (pin "2") (pinfunction "2_2") (pintype "passive"))
      (node (ref "D1") (pin "A") (pinfunction "A_A") (pintype "passive"))
      (node (ref "IC1") (pin "6") (pinfunction "INH_6") (pintype "input"))
      (node (ref "IC1") (pin "8") (pinfunction "GND_8") (pintype "power_in"))
      (node (ref "IC10") (pin "2") (pinfunction "GNDSIG_2") (pintype "input"))
      (node (ref "IC10") (pin "3") (pinfunction "~{ON/OFF}_3") (pintype "input"))
      (node (ref "IC10") (pin "4") (pinfunction "GND_4") (pintype "power_in"))
      (node (ref "IC3") (pin "13") (pinfunction "G_13") (pintype "input"))
      (node (ref "IC3") (pin "8") (pinfunction "GND_8") (pintype "power_in"))
      (node (ref "IC4") (pin "6") (pinfunction "INH_6") (pintype "input"))
      (node (ref "IC4") (pin "8") (pinfunction "GND_8") (pintype "power_in"))
      (node (ref "IC5") (pin "13") (pinfunction "G_13") (pintype "input"))
      (node (ref "IC5") (pin "8") (pinfunction "GND_8") (pintype "power_in"))
      (node (ref "IC6") (pin "11") (pinfunction "V-_11") (pintype "power_in"))
      (node (ref "IC7") (pin "2") (pinfunction "GND_2") (pintype "power_in"))
      (node (ref "IC9") (pin "11") (pinfunction "V-_11") (pintype "power_in"))
      (node (ref "J1") (pin "3") (pinfunction "3_3") (pintype "passive"))
      (node (ref "J1") (pin "6") (pinfunction "6_6") (pintype "passive"))
      (node (ref "J1") (pin "7") (pinfunction "7_7") (pintype "passive"))
      (node (ref "J2") (pin "3") (pinfunction "3_3") (pintype "passive"))
      (node (ref "J2") (pin "6") (pinfunction "6_6") (pintype "passive"))
      (node (ref "J2") (pin "7") (pinfunction "7_7") (pintype "passive"))
      (node (ref "J3") (pin "1") (pinfunction "1_1") (pintype "passive"))
      (node (ref "JP10") (pin "4") (pinfunction "4_4") (pintype "passive"))
      (node (ref "JP11") (pin "5") (pinfunction "5_5") (pintype "passive"))
      (node (ref "JP11") (pin "6") (pinfunction "6_6") (pintype "passive"))
      (node (ref "JP12") (pin "5") (pinfunction "5_5") (pintype "passive"))
      (node (ref "JP12") (pin "6") (pinfunction "6_6") (pintype "passive"))
      (node (ref "JP13") (pin "5") (pinfunction "5_5") (pintype "passive"))
      (node (ref "JP14") (pin "5") (pinfunction "5_5") (pintype "passive"))
      (node (ref "JP15") (pin "5") (pinfunction "5_5") (pintype "passive"))
      (node (ref "JP16") (pin "5") (pinfunction "5_5") (pintype "passive"))
      (node (ref "JP16") (pin "6") (pinfunction "6_6") (pintype "passive"))
      (node (ref "JP7") (pin "5") (pinfunction "5_5") (pintype "passive"))
      (node (ref "JP7") (pin "6") (pinfunction "6_6") (pintype "passive"))
      (node (ref "JP8") (pin "4") (pinfunction "4_4") (pintype "passive"))
      (node (ref "Q1") (pin "2") (pinfunction "S_2") (pintype "passive"))
      (node (ref "Q10") (pin "2") (pinfunction "S_2") (pintype "passive"))
      (node (ref "Q11") (pin "2") (pinfunction "S_2") (pintype "passive"))
      (node (ref "Q12") (pin "2") (pinfunction "S_2") (pintype "passive"))
      (node (ref "Q13") (pin "2") (pinfunction "S_2") (pintype "passive"))
      (node (ref "Q14") (pin "2") (pinfunction "S_2") (pintype "passive"))
      (node (ref "Q15") (pin "2") (pinfunction "S_2") (pintype "passive"))
      (node (ref "Q16") (pin "2") (pinfunction "S_2") (pintype "passive"))
      (node (ref "Q2") (pin "2") (pinfunction "S_2") (pintype "passive"))
      (node (ref "Q3") (pin "2") (pinfunction "S_2") (pintype "passive"))
      (node (ref "Q4") (pin "2") (pinfunction "S_2") (pintype "passive"))
      (node (ref "Q5") (pin "2") (pinfunction "S_2") (pintype "passive"))
      (node (ref "Q6") (pin "2") (pinfunction "S_2") (pintype "passive"))
      (node (ref "Q7") (pin "2") (pinfunction "S_2") (pintype "passive"))
      (node (ref "Q8") (pin "2") (pinfunction "S_2") (pintype "passive"))
      (node (ref "Q9") (pin "2") (pinfunction "S_2") (pintype "passive"))
      (node (ref "R2") (pin "1") (pinfunction "1_1") (pintype "passive"))
      (node (ref "R61") (pin "2") (pinfunction "2_2") (pintype "passive"))
      (node (ref "SJ12") (pin "P$2") (pinfunction "2_P$2") (pintype "passive"))
      (node (ref "SJ3") (pin "2") (pinfunction "2_2") (pintype "passive"))
      (node (ref "SJ6") (pin "P$2") (pinfunction "2_P$2") (pintype "passive"))
      (node (ref "SJ9") (pin "2") (pinfunction "2_2") (pintype "passive"))
      (node (ref "U$1") (pin "GND3") (pinfunction "GND3_GND3") (pintype "power_in"))
      (node (ref "U$1") (pin "GND5") (pinfunction "GND5_GND5") (pintype "power_in"))
      (node (ref "U$1") (pin "GND6") (pinfunction "GND6_GND6") (pintype "power_in"))
      (node (ref "U$1") (pin "GND7") (pinfunction "GND7_GND7") (pintype "power_in"))
      (node (ref "U$1") (pin "GND8") (pinfunction "GND8_GND8") (pintype "power_in"))
      (node (ref "U$2") (pin "3") (pinfunction "VSS_3") (pintype "power_in"))
      (node (ref "U$3") (pin "3") (pinfunction "VSS_3") (pintype "power_in"))
      (node (ref "U$4") (pin "3") (pinfunction "VSS_3") (pintype "power_in"))
      (node (ref "U$5") (pin "3") (pinfunction "VSS_3") (pintype "power_in"))
      (node (ref "U$6") (pin "2") (pinfunction "VSS_2") (pintype "power_in"))
      (node (ref "X1") (pin "2") (pinfunction "2_2") (pintype "passive"))
    )
    (net (code "23") (name "I2CSCL") (class "Default")
      (node (ref "JP8") (pin "2") (pinfunction "2_2") (pintype "passive"))
      (node (ref "R63") (pin "2") (pinfunction "2_2") (pintype "passive"))
      (node (ref "U$1") (pin "PB6") (pinfunction "PB6_PB6") (pintype "bidirectional"))
    )
    (net (code "24") (name "I2CSDA") (class "Default")
      (node (ref "JP8") (pin "1") (pinfunction "1_1") (pintype "passive"))
      (node (ref "R62") (pin "2") (pinfunction "2_2") (pintype "passive"))
      (node (ref "U$1") (pin "PB7") (pinfunction "PB7_PB7") (pintype "bidirectional"))
    )
    (net (code "25") (name "ILAT") (class "Default")
      (node (ref "IC1") (pin "15") (pinfunction "SH/~{LD}_15") (pintype "input"))
      (node (ref "IC4") (pin "15") (pinfunction "SH/~{LD}_15") (pintype "input"))
      (node (ref "U$1") (pin "PA6") (pinfunction "PA6_PA6") (pintype "bidirectional"))
    )
    (net (code "26") (name "MISO") (class "Default")
      (node (ref "JP9") (pin "1") (pinfunction "1_1") (pintype "passive"))
      (node (ref "U$1") (pin "PB4") (pinfunction "PB4_PB4") (pintype "bidirectional"))
    )
    (net (code "27") (name "MISO2") (class "Default")
      (node (ref "IC4") (pin "13") (pinfunction "QH_13") (pintype "output"))
      (node (ref "SJ13") (pin "P$2") (pinfunction "2_P$2") (pintype "passive"))
      (node (ref "U$1") (pin "PC2") (pinfunction "PC2_PC2") (pintype "bidirectional"))
    )
    (net (code "28") (name "MOSI") (class "Default")
      (node (ref "IC5") (pin "14") (pinfunction "SER_14") (pintype "input"))
      (node (ref "R20") (pin "1") (pinfunction "1_1") (pintype "passive"))
      (node (ref "SJ15") (pin "1") (pinfunction "1_1") (pintype "passive"))
      (node (ref "SJ17") (pin "P$2") (pinfunction "2_P$2") (pintype "passive"))
      (node (ref "U$1") (pin "PB5") (pinfunction "PB5_PB5") (pintype "bidirectional"))
    )
    (net (code "29") (name "Net-(AP1509-VOUT)") (class "Default")
      (node (ref "AP1509") (pin "2") (pinfunction "VOUT_2") (pintype "bidirectional"))
      (node (ref "D1") (pin "C") (pinfunction "C_C") (pintype "passive"))
      (node (ref "IC10") (pin "7") (pinfunction "OUT_7") (pintype "passive"))
      (node (ref "L1") (pin "2") (pinfunction "2_2") (pintype "passive"))
    )
    (net (code "30") (name "Net-(D2-PadA)") (class "Default")
      (node (ref "D2") (pin "A") (pinfunction "A_A") (pintype "passive"))
      (node (ref "JP4") (pin "4") (pinfunction "4_4") (pintype "passive"))
    )
    (net (code "31") (name "Net-(D2-PadC)") (class "Default")
      (node (ref "D2") (pin "C") (pinfunction "C_C") (pintype "passive"))
      (node (ref "JP4") (pin "1") (pinfunction "1_1") (pintype "passive"))
    )
    (net (code "32") (name "Net-(IC1A-A)") (class "Default")
      (node (ref "IC1") (pin "2") (pinfunction "A_2") (pintype "input"))
      (node (ref "R36") (pin "1") (pinfunction "1_1") (pintype "passive"))
      (node (ref "RN4") (pin "9") (pinfunction "2_9") (pintype "passive"))
    )
    (net (code "33") (name "Net-(IC1A-B)") (class "Default")
      (node (ref "IC1") (pin "3") (pinfunction "B_3") (pintype "input"))
      (node (ref "R37") (pin "1") (pinfunction "1_1") (pintype "passive"))
      (node (ref "RN4") (pin "10") (pinfunction "2_10") (pintype "passive"))
    )
    (net (code "34") (name "Net-(IC1A-C)") (class "Default")
      (node (ref "IC1") (pin "4") (pinfunction "C_4") (pintype "input"))
      (node (ref "R38") (pin "1") (pinfunction "1_1") (pintype "passive"))
      (node (ref "RN4") (pin "11") (pinfunction "2_11") (pintype "passive"))
    )
    (net (code "35") (name "Net-(IC1A-D)") (class "Default")
      (node (ref "IC1") (pin "5") (pinfunction "D_5") (pintype "input"))
      (node (ref "R39") (pin "1") (pinfunction "1_1") (pintype "passive"))
      (node (ref "RN4") (pin "12") (pinfunction "2_12") (pintype "passive"))
    )
    (net (code "36") (name "Net-(IC1A-E)") (class "Default")
      (node (ref "IC1") (pin "10") (pinfunction "E_10") (pintype "input"))
      (node (ref "R41") (pin "1") (pinfunction "1_1") (pintype "passive"))
      (node (ref "RN4") (pin "13") (pinfunction "2_13") (pintype "passive"))
    )
    (net (code "37") (name "Net-(IC1A-F)") (class "Default")
      (node (ref "IC1") (pin "11") (pinfunction "F_11") (pintype "input"))
      (node (ref "R42") (pin "1") (pinfunction "1_1") (pintype "passive"))
      (node (ref "RN4") (pin "14") (pinfunction "2_14") (pintype "passive"))
    )
    (net (code "38") (name "Net-(IC1A-G)") (class "Default")
      (node (ref "IC1") (pin "12") (pinfunction "G_12") (pintype "input"))
      (node (ref "R43") (pin "1") (pinfunction "1_1") (pintype "passive"))
      (node (ref "RN4") (pin "15") (pinfunction "2_15") (pintype "passive"))
    )
    (net (code "39") (name "Net-(IC1A-H)") (class "Default")
      (node (ref "IC1") (pin "14") (pinfunction "H_14") (pintype "input"))
      (node (ref "R44") (pin "1") (pinfunction "1_1") (pintype "passive"))
      (node (ref "RN4") (pin "16") (pinfunction "2_16") (pintype "passive"))
    )
    (net (code "40") (name "Net-(IC2-CD+)") (class "Default")
      (node (ref "IC2") (pin "10") (pinfunction "CD+_10") (pintype "passive"))
      (node (ref "SJ4") (pin "P$1") (pinfunction "1_P$1") (pintype "passive"))
      (node (ref "SJ5") (pin "P$1") (pinfunction "1_P$1") (pintype "passive"))
      (node (ref "SJ6") (pin "P$1") (pinfunction "1_P$1") (pintype "passive"))
    )
    (net (code "41") (name "Net-(IC2-GND)") (class "Default")
      (node (ref "IC2") (pin "9") (pinfunction "GND_9") (pintype "power_in"))
      (node (ref "SJ1") (pin "P$1") (pinfunction "1_P$1") (pintype "passive"))
      (node (ref "SJ2") (pin "P$1") (pinfunction "1_P$1") (pintype "passive"))
      (node (ref "SJ3") (pin "1") (pinfunction "1_1") (pintype "passive"))
    )
    (net (code "42") (name "Net-(IC2-I1)") (class "Default")
      (node (ref "IC2") (pin "1") (pinfunction "I1_1") (pintype "input"))
      (node (ref "IC5") (pin "15") (pinfunction "QA_15") (pintype "tri_state"))
      (node (ref "R3") (pin "1") (pinfunction "1_1") (pintype "passive"))
    )
    (net (code "43") (name "Net-(IC2-I2)") (class "Default")
      (node (ref "IC2") (pin "2") (pinfunction "I2_2") (pintype "input"))
      (node (ref "IC5") (pin "1") (pinfunction "QB_1") (pintype "tri_state"))
      (node (ref "R4") (pin "1") (pinfunction "1_1") (pintype "passive"))
    )
    (net (code "44") (name "Net-(IC2-I3)") (class "Default")
      (node (ref "IC2") (pin "3") (pinfunction "I3_3") (pintype "input"))
      (node (ref "IC5") (pin "2") (pinfunction "QC_2") (pintype "tri_state"))
      (node (ref "R5") (pin "1") (pinfunction "1_1") (pintype "passive"))
    )
    (net (code "45") (name "Net-(IC2-I4)") (class "Default")
      (node (ref "IC2") (pin "4") (pinfunction "I4_4") (pintype "input"))
      (node (ref "IC5") (pin "3") (pinfunction "QD_3") (pintype "tri_state"))
      (node (ref "R6") (pin "1") (pinfunction "1_1") (pintype "passive"))
    )
    (net (code "46") (name "Net-(IC2-I5)") (class "Default")
      (node (ref "IC2") (pin "5") (pinfunction "I5_5") (pintype "input"))
      (node (ref "IC5") (pin "4") (pinfunction "QE_4") (pintype "tri_state"))
      (node (ref "R7") (pin "1") (pinfunction "1_1") (pintype "passive"))
    )
    (net (code "47") (name "Net-(IC2-I6)") (class "Default")
      (node (ref "IC2") (pin "6") (pinfunction "I6_6") (pintype "input"))
      (node (ref "IC5") (pin "5") (pinfunction "QF_5") (pintype "tri_state"))
      (node (ref "R8") (pin "1") (pinfunction "1_1") (pintype "passive"))
    )
    (net (code "48") (name "Net-(IC2-I7)") (class "Default")
      (node (ref "IC2") (pin "7") (pinfunction "I7_7") (pintype "input"))
      (node (ref "IC5") (pin "6") (pinfunction "QG_6") (pintype "tri_state"))
      (node (ref "R9") (pin "1") (pinfunction "1_1") (pintype "passive"))
    )
    (net (code "49") (name "Net-(IC2-I8)") (class "Default")
      (node (ref "IC2") (pin "8") (pinfunction "I8_8") (pintype "input"))
      (node (ref "IC5") (pin "7") (pinfunction "QH_7") (pintype "tri_state"))
      (node (ref "R10") (pin "1") (pinfunction "1_1") (pintype "passive"))
    )
    (net (code "50") (name "Net-(IC2-O1)") (class "Default")
      (node (ref "IC2") (pin "18") (pinfunction "O1_18") (pintype "open_collector"))
      (node (ref "JP1") (pin "1") (pinfunction "1_1") (pintype "passive"))
      (node (ref "Q1") (pin "3") (pinfunction "D_3") (pintype "passive"))
    )
    (net (code "51") (name "Net-(IC2-O2)") (class "Default")
      (node (ref "IC2") (pin "17") (pinfunction "O2_17") (pintype "open_collector"))
      (node (ref "JP1") (pin "2") (pinfunction "2_2") (pintype "passive"))
      (node (ref "Q2") (pin "3") (pinfunction "D_3") (pintype "passive"))
    )
    (net (code "52") (name "Net-(IC2-O3)") (class "Default")
      (node (ref "IC2") (pin "16") (pinfunction "O3_16") (pintype "open_collector"))
      (node (ref "JP1") (pin "3") (pinfunction "3_3") (pintype "passive"))
      (node (ref "Q3") (pin "3") (pinfunction "D_3") (pintype "passive"))
    )
    (net (code "53") (name "Net-(IC2-O4)") (class "Default")
      (node (ref "IC2") (pin "15") (pinfunction "O4_15") (pintype "open_collector"))
      (node (ref "JP1") (pin "4") (pinfunction "4_4") (pintype "passive"))
      (node (ref "Q4") (pin "3") (pinfunction "D_3") (pintype "passive"))
    )
    (net (code "54") (name "Net-(IC2-O5)") (class "Default")
      (node (ref "IC2") (pin "14") (pinfunction "O5_14") (pintype "open_collector"))
      (node (ref "JP1") (pin "5") (pinfunction "5_5") (pintype "passive"))
      (node (ref "Q5") (pin "3") (pinfunction "D_3") (pintype "passive"))
    )
    (net (code "55") (name "Net-(IC2-O6)") (class "Default")
      (node (ref "IC2") (pin "13") (pinfunction "O6_13") (pintype "open_collector"))
      (node (ref "JP1") (pin "6") (pinfunction "6_6") (pintype "passive"))
      (node (ref "Q6") (pin "3") (pinfunction "D_3") (pintype "passive"))
    )
    (net (code "56") (name "Net-(IC2-O7)") (class "Default")
      (node (ref "IC2") (pin "12") (pinfunction "O7_12") (pintype "open_collector"))
      (node (ref "JP1") (pin "7") (pinfunction "7_7") (pintype "passive"))
      (node (ref "Q7") (pin "3") (pinfunction "D_3") (pintype "passive"))
    )
    (net (code "57") (name "Net-(IC2-O8)") (class "Default")
      (node (ref "IC2") (pin "11") (pinfunction "O8_11") (pintype "open_collector"))
      (node (ref "JP1") (pin "8") (pinfunction "8_8") (pintype "passive"))
      (node (ref "Q8") (pin "3") (pinfunction "D_3") (pintype "passive"))
    )
    (net (code "58") (name "Net-(IC3A-QA)") (class "Default")
      (node (ref "IC3") (pin "15") (pinfunction "QA_15") (pintype "tri_state"))
      (node (ref "IC8") (pin "1") (pinfunction "I1_1") (pintype "input"))
      (node (ref "R11") (pin "1") (pinfunction "1_1") (pintype "passive"))
    )
    (net (code "59") (name "Net-(IC3A-QB)") (class "Default")
      (node (ref "IC3") (pin "1") (pinfunction "QB_1") (pintype "tri_state"))
      (node (ref "IC8") (pin "2") (pinfunction "I2_2") (pintype "input"))
      (node (ref "R12") (pin "1") (pinfunction "1_1") (pintype "passive"))
    )
    (net (code "60") (name "Net-(IC3A-QC)") (class "Default")
      (node (ref "IC3") (pin "2") (pinfunction "QC_2") (pintype "tri_state"))
      (node (ref "IC8") (pin "3") (pinfunction "I3_3") (pintype "input"))
      (node (ref "R13") (pin "1") (pinfunction "1_1") (pintype "passive"))
    )
    (net (code "61") (name "Net-(IC3A-QD)") (class "Default")
      (node (ref "IC3") (pin "3") (pinfunction "QD_3") (pintype "tri_state"))
      (node (ref "IC8") (pin "4") (pinfunction "I4_4") (pintype "input"))
      (node (ref "R14") (pin "1") (pinfunction "1_1") (pintype "passive"))
    )
    (net (code "62") (name "Net-(IC3A-QE)") (class "Default")
      (node (ref "IC3") (pin "4") (pinfunction "QE_4") (pintype "tri_state"))
      (node (ref "IC8") (pin "5") (pinfunction "I5_5") (pintype "input"))
      (node (ref "R15") (pin "1") (pinfunction "1_1") (pintype "passive"))
    )
    (net (code "63") (name "Net-(IC3A-QF)") (class "Default")
      (node (ref "IC3") (pin "5") (pinfunction "QF_5") (pintype "tri_state"))
      (node (ref "IC8") (pin "6") (pinfunction "I6_6") (pintype "input"))
      (node (ref "R16") (pin "1") (pinfunction "1_1") (pintype "passive"))
    )
    (net (code "64") (name "Net-(IC3A-QG)") (class "Default")
      (node (ref "IC3") (pin "6") (pinfunction "QG_6") (pintype "tri_state"))
      (node (ref "IC8") (pin "7") (pinfunction "I7_7") (pintype "input"))
      (node (ref "R17") (pin "1") (pinfunction "1_1") (pintype "passive"))
    )
    (net (code "65") (name "Net-(IC3A-QH)") (class "Default")
      (node (ref "IC3") (pin "7") (pinfunction "QH_7") (pintype "tri_state"))
      (node (ref "IC8") (pin "8") (pinfunction "I8_8") (pintype "input"))
      (node (ref "R18") (pin "1") (pinfunction "1_1") (pintype "passive"))
    )
    (net (code "66") (name "Net-(IC4A-A)") (class "Default")
      (node (ref "IC4") (pin "2") (pinfunction "A_2") (pintype "input"))
      (node (ref "R28") (pin "1") (pinfunction "1_1") (pintype "passive"))
      (node (ref "RN1") (pin "9") (pinfunction "2_9") (pintype "passive"))
    )
    (net (code "67") (name "Net-(IC4A-B)") (class "Default")
      (node (ref "IC4") (pin "3") (pinfunction "B_3") (pintype "input"))
      (node (ref "R29") (pin "1") (pinfunction "1_1") (pintype "passive"))
      (node (ref "RN1") (pin "10") (pinfunction "2_10") (pintype "passive"))
    )
    (net (code "68") (name "Net-(IC4A-C)") (class "Default")
      (node (ref "IC4") (pin "4") (pinfunction "C_4") (pintype "input"))
      (node (ref "R30") (pin "1") (pinfunction "1_1") (pintype "passive"))
      (node (ref "RN1") (pin "11") (pinfunction "2_11") (pintype "passive"))
    )
    (net (code "69") (name "Net-(IC4A-D)") (class "Default")
      (node (ref "IC4") (pin "5") (pinfunction "D_5") (pintype "input"))
      (node (ref "R31") (pin "1") (pinfunction "1_1") (pintype "passive"))
      (node (ref "RN1") (pin "12") (pinfunction "2_12") (pintype "passive"))
    )
    (net (code "70") (name "Net-(IC4A-E)") (class "Default")
      (node (ref "IC4") (pin "10") (pinfunction "E_10") (pintype "input"))
      (node (ref "R32") (pin "1") (pinfunction "1_1") (pintype "passive"))
      (node (ref "RN1") (pin "13") (pinfunction "2_13") (pintype "passive"))
    )
    (net (code "71") (name "Net-(IC4A-F)") (class "Default")
      (node (ref "IC4") (pin "11") (pinfunction "F_11") (pintype "input"))
      (node (ref "R33") (pin "1") (pinfunction "1_1") (pintype "passive"))
      (node (ref "RN1") (pin "14") (pinfunction "2_14") (pintype "passive"))
    )
    (net (code "72") (name "Net-(IC4A-G)") (class "Default")
      (node (ref "IC4") (pin "12") (pinfunction "G_12") (pintype "input"))
      (node (ref "R34") (pin "1") (pinfunction "1_1") (pintype "passive"))
      (node (ref "RN1") (pin "15") (pinfunction "2_15") (pintype "passive"))
    )
    (net (code "73") (name "Net-(IC4A-H)") (class "Default")
      (node (ref "IC4") (pin "14") (pinfunction "H_14") (pintype "input"))
      (node (ref "R35") (pin "1") (pinfunction "1_1") (pintype "passive"))
      (node (ref "RN1") (pin "16") (pinfunction "2_16") (pintype "passive"))
    )
    (net (code "74") (name "Net-(IC6A--IN)") (class "Default")
      (node (ref "IC6") (pin "13") (pinfunction "-IN_13") (pintype "input"))
      (node (ref "IC6") (pin "2") (pinfunction "-IN_2") (pintype "input"))
      (node (ref "IC6") (pin "6") (pinfunction "-IN_6") (pintype "input"))
      (node (ref "IC6") (pin "9") (pinfunction "-IN_9") (pintype "input"))
      (node (ref "IC9") (pin "13") (pinfunction "-IN_13") (pintype "input"))
      (node (ref "IC9") (pin "2") (pinfunction "-IN_2") (pintype "input"))
      (node (ref "IC9") (pin "6") (pinfunction "-IN_6") (pintype "input"))
      (node (ref "IC9") (pin "9") (pinfunction "-IN_9") (pintype "input"))
      (node (ref "R1") (pin "1") (pinfunction "1_1") (pintype "passive"))
      (node (ref "R2") (pin "2") (pinfunction "2_2") (pintype "passive"))
    )
    (net (code "75") (name "Net-(IC6A-OUT)") (class "Default")
      (node (ref "IC6") (pin "1") (pinfunction "OUT_1") (pintype "output"))
      (node (ref "JP15") (pin "3") (pinfunction "3_3") (pintype "passive"))
      (node (ref "JP5") (pin "3") (pinfunction "3_3") (pintype "passive"))
      (node (ref "U$5") (pin "5") (pinfunction "O_5") (pintype "output"))
    )
    (net (code "76") (name "Net-(IC6B-OUT)") (class "Default")
      (node (ref "IC6") (pin "7") (pinfunction "OUT_7") (pintype "output"))
      (node (ref "JP15") (pin "1") (pinfunction "1_1") (pintype "passive"))
      (node (ref "JP5") (pin "1") (pinfunction "1_1") (pintype "passive"))
      (node (ref "U$4") (pin "7") (pinfunction "O_7") (pintype "output"))
    )
    (net (code "77") (name "Net-(IC6C-OUT)") (class "Default")
      (node (ref "IC6") (pin "8") (pinfunction "OUT_8") (pintype "output"))
      (node (ref "JP15") (pin "2") (pinfunction "2_2") (pintype "passive"))
      (node (ref "JP5") (pin "2") (pinfunction "2_2") (pintype "passive"))
      (node (ref "U$4") (pin "5") (pinfunction "O_5") (pintype "output"))
    )
    (net (code "78") (name "Net-(IC6D-OUT)") (class "Default")
      (node (ref "IC6") (pin "14") (pinfunction "OUT_14") (pintype "output"))
      (node (ref "JP15") (pin "4") (pinfunction "4_4") (pintype "passive"))
      (node (ref "JP5") (pin "4") (pinfunction "4_4") (pintype "passive"))
      (node (ref "U$5") (pin "7") (pinfunction "O_7") (pintype "output"))
    )
    (net (code "79") (name "Net-(IC7-RS)") (class "Default")
      (node (ref "IC7") (pin "8") (pinfunction "RS_8") (pintype "input"))
      (node (ref "R61") (pin "1") (pinfunction "1_1") (pintype "passive"))
      (node (ref "U$6") (pin "8") (pinfunction "RS_8") (pintype "bidirectional"))
    )
    (net (code "80") (name "Net-(IC7-VREF)") (class "Default")
      (node (ref "IC7") (pin "5") (pinfunction "VREF_5") (pintype "output"))
      (node (ref "SJ18") (pin "P$2") (pinfunction "2_P$2") (pintype "passive"))
      (node (ref "U$6") (pin "5") (pinfunction "VREF_5") (pintype "bidirectional"))
    )
    (net (code "81") (name "Net-(IC8-CD+)") (class "Default")
      (node (ref "IC8") (pin "10") (pinfunction "CD+_10") (pintype "passive"))
      (node (ref "SJ10") (pin "P$1") (pinfunction "1_P$1") (pintype "passive"))
      (node (ref "SJ11") (pin "P$1") (pinfunction "1_P$1") (pintype "passive"))
      (node (ref "SJ12") (pin "P$1") (pinfunction "1_P$1") (pintype "passive"))
    )
    (net (code "82") (name "Net-(IC8-GND)") (class "Default")
      (node (ref "IC8") (pin "9") (pinfunction "GND_9") (pintype "power_in"))
      (node (ref "SJ7") (pin "P$1") (pinfunction "1_P$1") (pintype "passive"))
      (node (ref "SJ8") (pin "P$1") (pinfunction "1_P$1") (pintype "passive"))
      (node (ref "SJ9") (pin "1") (pinfunction "1_1") (pintype "passive"))
    )
    (net (code "83") (name "Net-(IC8-O1)") (class "Default")
      (node (ref "IC8") (pin "18") (pinfunction "O1_18") (pintype "open_collector"))
      (node (ref "JP6") (pin "1") (pinfunction "1_1") (pintype "passive"))
      (node (ref "Q9") (pin "3") (pinfunction "D_3") (pintype "passive"))
    )
    (net (code "84") (name "Net-(IC8-O2)") (class "Default")
      (node (ref "IC8") (pin "17") (pinfunction "O2_17") (pintype "open_collector"))
      (node (ref "JP6") (pin "2") (pinfunction "2_2") (pintype "passive"))
      (node (ref "Q10") (pin "3") (pinfunction "D_3") (pintype "passive"))
    )
    (net (code "85") (name "Net-(IC8-O3)") (class "Default")
      (node (ref "IC8") (pin "16") (pinfunction "O3_16") (pintype "open_collector"))
      (node (ref "JP6") (pin "3") (pinfunction "3_3") (pintype "passive"))
      (node (ref "Q11") (pin "3") (pinfunction "D_3") (pintype "passive"))
    )
    (net (code "86") (name "Net-(IC8-O4)") (class "Default")
      (node (ref "IC8") (pin "15") (pinfunction "O4_15") (pintype "open_collector"))
      (node (ref "JP6") (pin "4") (pinfunction "4_4") (pintype "passive"))
      (node (ref "Q12") (pin "3") (pinfunction "D_3") (pintype "passive"))
    )
    (net (code "87") (name "Net-(IC8-O5)") (class "Default")
      (node (ref "IC8") (pin "14") (pinfunction "O5_14") (pintype "open_collector"))
      (node (ref "JP6") (pin "5") (pinfunction "5_5") (pintype "passive"))
      (node (ref "Q13") (pin "3") (pinfunction "D_3") (pintype "passive"))
    )
    (net (code "88") (name "Net-(IC8-O6)") (class "Default")
      (node (ref "IC8") (pin "13") (pinfunction "O6_13") (pintype "open_collector"))
      (node (ref "JP6") (pin "6") (pinfunction "6_6") (pintype "passive"))
      (node (ref "Q14") (pin "3") (pinfunction "D_3") (pintype "passive"))
    )
    (net (code "89") (name "Net-(IC8-O7)") (class "Default")
      (node (ref "IC8") (pin "12") (pinfunction "O7_12") (pintype "open_collector"))
      (node (ref "JP6") (pin "7") (pinfunction "7_7") (pintype "passive"))
      (node (ref "Q15") (pin "3") (pinfunction "D_3") (pintype "passive"))
    )
    (net (code "90") (name "Net-(IC8-O8)") (class "Default")
      (node (ref "IC8") (pin "11") (pinfunction "O8_11") (pintype "open_collector"))
      (node (ref "JP6") (pin "8") (pinfunction "8_8") (pintype "passive"))
      (node (ref "Q16") (pin "3") (pinfunction "D_3") (pintype "passive"))
    )
    (net (code "91") (name "Net-(IC9A-OUT)") (class "Default")
      (node (ref "IC9") (pin "1") (pinfunction "OUT_1") (pintype "output"))
      (node (ref "JP15") (pin "9") (pinfunction "9_9") (pintype "passive"))
      (node (ref "JP5") (pin "7") (pinfunction "7_7") (pintype "passive"))
      (node (ref "U$3") (pin "5") (pinfunction "O_5") (pintype "output"))
    )
    (net (code "92") (name "Net-(IC9B-OUT)") (class "Default")
      (node (ref "IC9") (pin "7") (pinfunction "OUT_7") (pintype "output"))
      (node (ref "JP15") (pin "7") (pinfunction "7_7") (pintype "passive"))
      (node (ref "JP5") (pin "5") (pinfunction "5_5") (pintype "passive"))
      (node (ref "U$2") (pin "7") (pinfunction "O_7") (pintype "output"))
    )
    (net (code "93") (name "Net-(IC9C-OUT)") (class "Default")
      (node (ref "IC9") (pin "8") (pinfunction "OUT_8") (pintype "output"))
      (node (ref "JP15") (pin "8") (pinfunction "8_8") (pintype "passive"))
      (node (ref "JP5") (pin "6") (pinfunction "6_6") (pintype "passive"))
      (node (ref "U$2") (pin "5") (pinfunction "O_5") (pintype "output"))
    )
    (net (code "94") (name "Net-(IC9D-OUT)") (class "Default")
      (node (ref "IC9") (pin "14") (pinfunction "OUT_14") (pintype "output"))
      (node (ref "JP15") (pin "10") (pinfunction "10_10") (pintype "passive"))
      (node (ref "JP5") (pin "8") (pinfunction "8_8") (pintype "passive"))
      (node (ref "U$3") (pin "7") (pinfunction "O_7") (pintype "output"))
    )
    (net (code "95") (name "Net-(J1-Pad4)") (class "Default")
      (node (ref "J1") (pin "4") (pinfunction "4_4") (pintype "passive"))
      (node (ref "J2") (pin "4") (pinfunction "4_4") (pintype "passive"))
    )
    (net (code "96") (name "Net-(J1-Pad5)") (class "Default")
      (node (ref "J1") (pin "5") (pinfunction "5_5") (pintype "passive"))
      (node (ref "J2") (pin "5") (pinfunction "5_5") (pintype "passive"))
    )
    (net (code "97") (name "Net-(J1-Pad8)") (class "Default")
      (node (ref "J1") (pin "8") (pinfunction "8_8") (pintype "passive"))
      (node (ref "J2") (pin "8") (pinfunction "8_8") (pintype "passive"))
      (node (ref "R40") (pin "1") (pinfunction "1_1") (pintype "passive"))
    )
    (net (code "98") (name "Net-(JP4-Pad3)") (class "Default")
      (node (ref "JP4") (pin "3") (pinfunction "3_3") (pintype "passive"))
      (node (ref "R40") (pin "2") (pinfunction "2_2") (pintype "passive"))
    )
    (net (code "99") (name "Net-(JP13-Pad1)") (class "Default")
      (node (ref "JP13") (pin "1") (pinfunction "1_1") (pintype "passive"))
      (node (ref "JP3") (pin "1") (pinfunction "1_1") (pintype "passive"))
      (node (ref "R44") (pin "2") (pinfunction "2_2") (pintype "passive"))
      (node (ref "R53") (pin "2") (pinfunction "2_2") (pintype "passive"))
      (node (ref "RN4") (pin "1") (pinfunction "1_1") (pintype "passive"))
      (node (ref "RN5") (pin "9") (pinfunction "9_9") (pintype "passive"))
    )
    (net (code "100") (name "Net-(JP14-Pad1)") (class "Default")
      (node (ref "JP14") (pin "1") (pinfunction "1_1") (pintype "passive"))
      (node (ref "JP2") (pin "1") (pinfunction "1_1") (pintype "passive"))
      (node (ref "R35") (pin "2") (pinfunction "2_2") (pintype "passive"))
      (node (ref "R45") (pin "2") (pinfunction "2_2") (pintype "passive"))
      (node (ref "RN1") (pin "1") (pinfunction "1_1") (pintype "passive"))
      (node (ref "RN2") (pin "9") (pinfunction "9_9") (pintype "passive"))
    )
    (net (code "101") (name "Net-(Q1-G)") (class "Default")
      (node (ref "Q1") (pin "1") (pinfunction "G_1") (pintype "passive"))
      (node (ref "R3") (pin "2") (pinfunction "2_2") (pintype "passive"))
    )
    (net (code "102") (name "Net-(Q2-G)") (class "Default")
      (node (ref "Q2") (pin "1") (pinfunction "G_1") (pintype "passive"))
      (node (ref "R4") (pin "2") (pinfunction "2_2") (pintype "passive"))
    )
    (net (code "103") (name "Net-(Q3-G)") (class "Default")
      (node (ref "Q3") (pin "1") (pinfunction "G_1") (pintype "passive"))
      (node (ref "R5") (pin "2") (pinfunction "2_2") (pintype "passive"))
    )
    (net (code "104") (name "Net-(Q4-G)") (class "Default")
      (node (ref "Q4") (pin "1") (pinfunction "G_1") (pintype "passive"))
      (node (ref "R6") (pin "2") (pinfunction "2_2") (pintype "passive"))
    )
    (net (code "105") (name "Net-(Q5-G)") (class "Default")
      (node (ref "Q5") (pin "1") (pinfunction "G_1") (pintype "passive"))
      (node (ref "R7") (pin "2") (pinfunction "2_2") (pintype "passive"))
    )
    (net (code "106") (name "Net-(Q6-G)") (class "Default")
      (node (ref "Q6") (pin "1") (pinfunction "G_1") (pintype "passive"))
      (node (ref "R8") (pin "2") (pinfunction "2_2") (pintype "passive"))
    )
    (net (code "107") (name "Net-(Q7-G)") (class "Default")
      (node (ref "Q7") (pin "1") (pinfunction "G_1") (pintype "passive"))
      (node (ref "R9") (pin "2") (pinfunction "2_2") (pintype "passive"))
    )
    (net (code "108") (name "Net-(Q8-G)") (class "Default")
      (node (ref "Q8") (pin "1") (pinfunction "G_1") (pintype "passive"))
      (node (ref "R10") (pin "2") (pinfunction "2_2") (pintype "passive"))
    )
    (net (code "109") (name "Net-(Q9-G)") (class "Default")
      (node (ref "Q9") (pin "1") (pinfunction "G_1") (pintype "passive"))
      (node (ref "R11") (pin "2") (pinfunction "2_2") (pintype "passive"))
    )
    (net (code "110") (name "Net-(Q10-G)") (class "Default")
      (node (ref "Q10") (pin "1") (pinfunction "G_1") (pintype "passive"))
      (node (ref "R12") (pin "2") (pinfunction "2_2") (pintype "passive"))
    )
    (net (code "111") (name "Net-(Q11-G)") (class "Default")
      (node (ref "Q11") (pin "1") (pinfunction "G_1") (pintype "passive"))
      (node (ref "R13") (pin "2") (pinfunction "2_2") (pintype "passive"))
    )
    (net (code "112") (name "Net-(Q12-G)") (class "Default")
      (node (ref "Q12") (pin "1") (pinfunction "G_1") (pintype "passive"))
      (node (ref "R14") (pin "2") (pinfunction "2_2") (pintype "passive"))
    )
    (net (code "113") (name "Net-(Q13-G)") (class "Default")
      (node (ref "Q13") (pin "1") (pinfunction "G_1") (pintype "passive"))
      (node (ref "R15") (pin "2") (pinfunction "2_2") (pintype "passive"))
    )
    (net (code "114") (name "Net-(Q14-G)") (class "Default")
      (node (ref "Q14") (pin "1") (pinfunction "G_1") (pintype "passive"))
      (node (ref "R16") (pin "2") (pinfunction "2_2") (pintype "passive"))
    )
    (net (code "115") (name "Net-(Q15-G)") (class "Default")
      (node (ref "Q15") (pin "1") (pinfunction "G_1") (pintype "passive"))
      (node (ref "R17") (pin "2") (pinfunction "2_2") (pintype "passive"))
    )
    (net (code "116") (name "Net-(Q16-G)") (class "Default")
      (node (ref "Q16") (pin "1") (pinfunction "G_1") (pintype "passive"))
      (node (ref "R18") (pin "2") (pinfunction "2_2") (pintype "passive"))
    )
    (net (code "117") (name "Net-(RN1B-1)") (class "Default")
      (node (ref "JP14") (pin "2") (pinfunction "2_2") (pintype "passive"))
      (node (ref "JP2") (pin "2") (pinfunction "2_2") (pintype "passive"))
      (node (ref "R34") (pin "2") (pinfunction "2_2") (pintype "passive"))
      (node (ref "R46") (pin "1") (pinfunction "1_1") (pintype "passive"))
      (node (ref "RN1") (pin "2") (pinfunction "1_2") (pintype "passive"))
      (node (ref "RN2") (pin "8") (pinfunction "8_8") (pintype "passive"))
    )
    (net (code "118") (name "Net-(RN1C-1)") (class "Default")
      (node (ref "JP14") (pin "3") (pinfunction "3_3") (pintype "passive"))
      (node (ref "JP2") (pin "3") (pinfunction "3_3") (pintype "passive"))
      (node (ref "R33") (pin "2") (pinfunction "2_2") (pintype "passive"))
      (node (ref "R47") (pin "1") (pinfunction "1_1") (pintype "passive"))
      (node (ref "RN1") (pin "3") (pinfunction "1_3") (pintype "passive"))
      (node (ref "RN2") (pin "7") (pinfunction "7_7") (pintype "passive"))
    )
    (net (code "119") (name "Net-(RN1D-1)") (class "Default")
      (node (ref "JP14") (pin "4") (pinfunction "4_4") (pintype "passive"))
      (node (ref "JP2") (pin "4") (pinfunction "4_4") (pintype "passive"))
      (node (ref "R32") (pin "2") (pinfunction "2_2") (pintype "passive"))
      (node (ref "R48") (pin "1") (pinfunction "1_1") (pintype "passive"))
      (node (ref "RN1") (pin "4") (pinfunction "1_4") (pintype "passive"))
      (node (ref "RN2") (pin "6") (pinfunction "6_6") (pintype "passive"))
    )
    (net (code "120") (name "Net-(RN1E-1)") (class "Default")
      (node (ref "JP14") (pin "7") (pinfunction "7_7") (pintype "passive"))
      (node (ref "JP2") (pin "5") (pinfunction "5_5") (pintype "passive"))
      (node (ref "R31") (pin "2") (pinfunction "2_2") (pintype "passive"))
      (node (ref "R49") (pin "1") (pinfunction "1_1") (pintype "passive"))
      (node (ref "RN1") (pin "5") (pinfunction "1_5") (pintype "passive"))
      (node (ref "RN2") (pin "5") (pinfunction "5_5") (pintype "passive"))
    )
    (net (code "121") (name "Net-(RN1F-1)") (class "Default")
      (node (ref "JP14") (pin "8") (pinfunction "8_8") (pintype "passive"))
      (node (ref "JP2") (pin "6") (pinfunction "6_6") (pintype "passive"))
      (node (ref "R30") (pin "2") (pinfunction "2_2") (pintype "passive"))
      (node (ref "R50") (pin "1") (pinfunction "1_1") (pintype "passive"))
      (node (ref "RN1") (pin "6") (pinfunction "1_6") (pintype "passive"))
      (node (ref "RN2") (pin "4") (pinfunction "4_4") (pintype "passive"))
    )
    (net (code "122") (name "Net-(RN1G-1)") (class "Default")
      (node (ref "JP14") (pin "9") (pinfunction "9_9") (pintype "passive"))
      (node (ref "JP2") (pin "7") (pinfunction "7_7") (pintype "passive"))
      (node (ref "R29") (pin "2") (pinfunction "2_2") (pintype "passive"))
      (node (ref "R51") (pin "1") (pinfunction "1_1") (pintype "passive"))
      (node (ref "RN1") (pin "7") (pinfunction "1_7") (pintype "passive"))
      (node (ref "RN2") (pin "3") (pinfunction "3_3") (pintype "passive"))
    )
    (net (code "123") (name "Net-(RN1H-1)") (class "Default")
      (node (ref "JP14") (pin "10") (pinfunction "10_10") (pintype "passive"))
      (node (ref "JP2") (pin "8") (pinfunction "8_8") (pintype "passive"))
      (node (ref "R28") (pin "2") (pinfunction "2_2") (pintype "passive"))
      (node (ref "R52") (pin "1") (pinfunction "1_1") (pintype "passive"))
      (node (ref "RN1") (pin "8") (pinfunction "1_8") (pintype "passive"))
      (node (ref "RN2") (pin "2") (pinfunction "2_2") (pintype "passive"))
    )
    (net (code "124") (name "Net-(RN4B-1)") (class "Default")
      (node (ref "JP13") (pin "2") (pinfunction "2_2") (pintype "passive"))
      (node (ref "JP3") (pin "2") (pinfunction "2_2") (pintype "passive"))
      (node (ref "R43") (pin "2") (pinfunction "2_2") (pintype "passive"))
      (node (ref "R54") (pin "2") (pinfunction "2_2") (pintype "passive"))
      (node (ref "RN4") (pin "2") (pinfunction "1_2") (pintype "passive"))
      (node (ref "RN5") (pin "8") (pinfunction "8_8") (pintype "passive"))
    )
    (net (code "125") (name "Net-(RN4C-1)") (class "Default")
      (node (ref "JP13") (pin "3") (pinfunction "3_3") (pintype "passive"))
      (node (ref "JP3") (pin "3") (pinfunction "3_3") (pintype "passive"))
      (node (ref "R42") (pin "2") (pinfunction "2_2") (pintype "passive"))
      (node (ref "R55") (pin "2") (pinfunction "2_2") (pintype "passive"))
      (node (ref "RN4") (pin "3") (pinfunction "1_3") (pintype "passive"))
      (node (ref "RN5") (pin "7") (pinfunction "7_7") (pintype "passive"))
    )
    (net (code "126") (name "Net-(RN4D-1)") (class "Default")
      (node (ref "JP13") (pin "4") (pinfunction "4_4") (pintype "passive"))
      (node (ref "JP3") (pin "4") (pinfunction "4_4") (pintype "passive"))
      (node (ref "R41") (pin "2") (pinfunction "2_2") (pintype "passive"))
      (node (ref "R56") (pin "2") (pinfunction "2_2") (pintype "passive"))
      (node (ref "RN4") (pin "4") (pinfunction "1_4") (pintype "passive"))
      (node (ref "RN5") (pin "6") (pinfunction "6_6") (pintype "passive"))
    )
    (net (code "127") (name "Net-(RN4E-1)") (class "Default")
      (node (ref "JP13") (pin "7") (pinfunction "7_7") (pintype "passive"))
      (node (ref "JP3") (pin "5") (pinfunction "5_5") (pintype "passive"))
      (node (ref "R39") (pin "2") (pinfunction "2_2") (pintype "passive"))
      (node (ref "R57") (pin "2") (pinfunction "2_2") (pintype "passive"))
      (node (ref "RN4") (pin "5") (pinfunction "1_5") (pintype "passive"))
      (node (ref "RN5") (pin "5") (pinfunction "5_5") (pintype "passive"))
    )
    (net (code "128") (name "Net-(RN4F-1)") (class "Default")
      (node (ref "JP13") (pin "8") (pinfunction "8_8") (pintype "passive"))
      (node (ref "JP3") (pin "6") (pinfunction "6_6") (pintype "passive"))
      (node (ref "R38") (pin "2") (pinfunction "2_2") (pintype "passive"))
      (node (ref "R58") (pin "2") (pinfunction "2_2") (pintype "passive"))
      (node (ref "RN4") (pin "6") (pinfunction "1_6") (pintype "passive"))
      (node (ref "RN5") (pin "4") (pinfunction "4_4") (pintype "passive"))
    )
    (net (code "129") (name "Net-(RN4G-1)") (class "Default")
      (node (ref "JP13") (pin "9") (pinfunction "9_9") (pintype "passive"))
      (node (ref "JP3") (pin "7") (pinfunction "7_7") (pintype "passive"))
      (node (ref "R37") (pin "2") (pinfunction "2_2") (pintype "passive"))
      (node (ref "R59") (pin "2") (pinfunction "2_2") (pintype "passive"))
      (node (ref "RN4") (pin "7") (pinfunction "1_7") (pintype "passive"))
      (node (ref "RN5") (pin "3") (pinfunction "3_3") (pintype "passive"))
    )
    (net (code "130") (name "Net-(RN4H-1)") (class "Default")
      (node (ref "JP13") (pin "10") (pinfunction "10_10") (pintype "passive"))
      (node (ref "JP3") (pin "8") (pinfunction "8_8") (pintype "passive"))
      (node (ref "R36") (pin "2") (pinfunction "2_2") (pintype "passive"))
      (node (ref "R60") (pin "2") (pinfunction "2_2") (pintype "passive"))
      (node (ref "RN4") (pin "8") (pinfunction "1_8") (pintype "passive"))
      (node (ref "RN5") (pin "2") (pinfunction "2_2") (pintype "passive"))
    )
    (net (code "131") (name "Net-(SJ13-1)") (class "Default")
      (node (ref "SJ13") (pin "P$1") (pinfunction "1_P$1") (pintype "passive"))
      (node (ref "U$1") (pin "PB14") (pinfunction "PB14_PB14") (pintype "bidirectional"))
    )
    (net (code "132") (name "Net-(SJ14-1)") (class "Default")
      (node (ref "SJ14") (pin "P$1") (pinfunction "1_P$1") (pintype "passive"))
      (node (ref "U$1") (pin "VIN2") (pinfunction "VIN2_VIN2") (pintype "power_in"))
    )
    (net (code "133") (name "Net-(SJ16-2)") (class "Default")
      (node (ref "JP9") (pin "2") (pinfunction "2_2") (pintype "passive"))
      (node (ref "SJ15") (pin "2") (pinfunction "2_2") (pintype "passive"))
      (node (ref "SJ16") (pin "P$2") (pinfunction "2_P$2") (pintype "passive"))
    )
    (net (code "134") (name "OLAT") (class "Default")
      (node (ref "IC3") (pin "12") (pinfunction "RCK_12") (pintype "input"))
      (node (ref "IC5") (pin "12") (pinfunction "RCK_12") (pintype "input"))
      (node (ref "R21") (pin "1") (pinfunction "1_1") (pintype "passive"))
      (node (ref "U$1") (pin "PA8") (pinfunction "PA8_PA8") (pintype "bidirectional"))
    )
    (net (code "135") (name "SCK") (class "Default")
      (node (ref "IC3") (pin "11") (pinfunction "SCK_11") (pintype "input"))
      (node (ref "IC5") (pin "11") (pinfunction "SCK_11") (pintype "input"))
      (node (ref "JP9") (pin "3") (pinfunction "3_3") (pintype "passive"))
      (node (ref "R19") (pin "1") (pinfunction "1_1") (pintype "passive"))
      (node (ref "U$1") (pin "PB3") (pinfunction "PB3_PB3") (pintype "bidirectional"))
    )
    (net (code "136") (name "SCK2") (class "Default")
      (node (ref "IC1") (pin "7") (pinfunction "CLK_7") (pintype "input"))
      (node (ref "IC4") (pin "7") (pinfunction "CLK_7") (pintype "input"))
      (node (ref "U$1") (pin "PB10") (pinfunction "PB10_PB10") (pintype "bidirectional"))
    )
    (net (code "137") (name "SLNK1") (class "Default")
      (node (ref "IC3") (pin "14") (pinfunction "SER_14") (pintype "input"))
      (node (ref "IC5") (pin "9") (pinfunction "QH*_9") (pintype "tri_state"))
      (node (ref "SJ17") (pin "P$1") (pinfunction "1_P$1") (pintype "passive"))
    )
    (net (code "138") (name "SLNK2") (class "Default")
      (node (ref "IC3") (pin "9") (pinfunction "QH*_9") (pintype "tri_state"))
      (node (ref "SJ16") (pin "P$1") (pinfunction "1_P$1") (pintype "passive"))
    )
    (net (code "139") (name "SLNK3") (class "Default")
      (node (ref "IC1") (pin "13") (pinfunction "QH_13") (pintype "output"))
      (node (ref "IC4") (pin "1") (pinfunction "SER_1") (pintype "input"))
    )
    (net (code "140") (name "SRV1") (class "Default")
      (node (ref "JP7") (pin "2") (pinfunction "2_2") (pintype "passive"))
      (node (ref "R25") (pin "2") (pinfunction "2_2") (pintype "passive"))
      (node (ref "U$1") (pin "PC9") (pinfunction "PC9_PC9") (pintype "bidirectional"))
    )
    (net (code "141") (name "SRV2") (class "Default")
      (node (ref "JP7") (pin "1") (pinfunction "1_1") (pintype "passive"))
      (node (ref "R24") (pin "2") (pinfunction "2_2") (pintype "passive"))
      (node (ref "U$1") (pin "PC7") (pinfunction "PC7_PC7") (pintype "bidirectional"))
    )
    (net (code "142") (name "SRV3") (class "Default")
      (node (ref "JP11") (pin "2") (pinfunction "2_2") (pintype "passive"))
      (node (ref "R26") (pin "2") (pinfunction "2_2") (pintype "passive"))
      (node (ref "U$1") (pin "PC8") (pinfunction "PC8_PC8") (pintype "bidirectional"))
    )
    (net (code "143") (name "SRV4") (class "Default")
      (node (ref "JP11") (pin "1") (pinfunction "1_1") (pintype "passive"))
      (node (ref "R27") (pin "2") (pinfunction "2_2") (pintype "passive"))
      (node (ref "U$1") (pin "PC6") (pinfunction "PC6_PC6") (pintype "bidirectional"))
    )
    (net (code "144") (name "SRV5") (class "Default")
      (node (ref "JP12") (pin "2") (pinfunction "2_2") (pintype "passive"))
      (node (ref "R64") (pin "2") (pinfunction "2_2") (pintype "passive"))
      (node (ref "U$1") (pin "PF1-PH1") (pinfunction "PF1-PH1_PF1-PH1") (pintype "bidirectional"))
    )
    (net (code "145") (name "SRV6") (class "Default")
      (node (ref "JP12") (pin "1") (pinfunction "1_1") (pintype "passive"))
      (node (ref "R65") (pin "2") (pinfunction "2_2") (pintype "passive"))
      (node (ref "U$1") (pin "PA15") (pinfunction "PA15_PA15") (pintype "bidirectional"))
    )
    (net (code "146") (name "SRV7") (class "Default")
      (node (ref "JP16") (pin "2") (pinfunction "2_2") (pintype "passive"))
      (node (ref "R66") (pin "2") (pinfunction "2_2") (pintype "passive"))
      (node (ref "U$1") (pin "PC12") (pinfunction "PC12_PC12") (pintype "bidirectional"))
    )
    (net (code "147") (name "SRV8") (class "Default")
      (node (ref "JP16") (pin "1") (pinfunction "1_1") (pintype "passive"))
      (node (ref "R67") (pin "2") (pinfunction "2_2") (pintype "passive"))
      (node (ref "U$1") (pin "PD2") (pinfunction "PD2_PD2") (pintype "bidirectional"))
    )
    (net (code "148") (name "TIN3") (class "Default")
      (node (ref "IC9") (pin "10") (pinfunction "+IN_10") (pintype "input"))
      (node (ref "U$1") (pin "PB15") (pinfunction "PB15_PB15") (pintype "bidirectional"))
      (node (ref "U$2") (pin "4") (pinfunction "I_4") (pintype "input"))
    )
    (net (code "149") (name "TIN4") (class "Default")
      (node (ref "IC9") (pin "12") (pinfunction "+IN_12") (pintype "input"))
      (node (ref "U$1") (pin "PB12") (pinfunction "PB12_PB12") (pintype "bidirectional"))
      (node (ref "U$3") (pin "2") (pinfunction "I_2") (pintype "input"))
    )
    (net (code "150") (name "V+") (class "Default")
      (node (ref "AP1509") (pin "3") (pinfunction "FB_3") (pintype "bidirectional"))
      (node (ref "C1") (pin "1") (pinfunction "1_1") (pintype "passive"))
      (node (ref "C2") (pin "+") (pinfunction "+_+") (pintype "passive"))
      (node (ref "IC10") (pin "1") (pinfunction "FB_1") (pintype "input"))
      (node (ref "L1") (pin "1") (pinfunction "1_1") (pintype "passive"))
      (node (ref "U$1") (pin "E5V") (pinfunction "E5V_E5V") (pintype "power_in"))
    )
    (net (code "151") (name "unconnected-(H1-MOUNT-PadB3,3)") (class "Default")
      (node (ref "H1") (pin "B3,3") (pinfunction "MOUNT_B3,3") (pintype "passive"))
    )
    (net (code "152") (name "unconnected-(H2-MOUNT-PadB3,3)") (class "Default")
      (node (ref "H2") (pin "B3,3") (pinfunction "MOUNT_B3,3") (pintype "passive"))
    )
    (net (code "153") (name "unconnected-(H3-MOUNT-PadB3,3)") (class "Default")
      (node (ref "H3") (pin "B3,3") (pinfunction "MOUNT_B3,3") (pintype "passive"))
    )
    (net (code "154") (name "unconnected-(H4-MOUNT-PadB3,3)") (class "Default")
      (node (ref "H4") (pin "B3,3") (pinfunction "MOUNT_B3,3") (pintype "passive"))
    )
    (net (code "155") (name "unconnected-(J3-Pad2)") (class "Default")
      (node (ref "J3") (pin "2") (pinfunction "2_2") (pintype "passive"))
    )
    (net (code "156") (name "unconnected-(U$1-PadBOOT0)") (class "Default")
      (node (ref "U$1") (pin "BOOT0") (pinfunction "BOOT0_BOOT0") (pintype "bidirectional"))
    )
    (net (code "157") (name "unconnected-(U$1-PadIOREF2)") (class "Default")
      (node (ref "U$1") (pin "IOREF2") (pinfunction "IOREF2_IOREF2") (pintype "input"))
    )
    (net (code "158") (name "unconnected-(U$1-PadNC1-PF7)") (class "Default")
      (node (ref "U$1") (pin "NC1-PF7") (pinfunction "NC1-PF7_NC1-PF7") (pintype "bidirectional"))
    )
    (net (code "159") (name "unconnected-(U$1-PadNC2-PF6)") (class "Default")
      (node (ref "U$1") (pin "NC2-PF6") (pinfunction "NC2-PF6_NC2-PF6") (pintype "bidirectional"))
    )
    (net (code "160") (name "unconnected-(U$1-PadNC3)") (class "Default")
      (node (ref "U$1") (pin "NC3") (pinfunction "NC3_NC3") (pintype "no_connect"))
    )
    (net (code "161") (name "unconnected-(U$1-PadNC4)") (class "Default")
      (node (ref "U$1") (pin "NC4") (pinfunction "NC4_NC4") (pintype "no_connect"))
    )
    (net (code "162") (name "unconnected-(U$1-PadNC5-PD8)") (class "Default")
      (node (ref "U$1") (pin "NC5-PD8") (pinfunction "NC5-PD8_NC5-PD8") (pintype "bidirectional"))
    )
    (net (code "163") (name "unconnected-(U$1-PadNC6-PB11)") (class "Default")
      (node (ref "U$1") (pin "NC6-PB11") (pinfunction "NC6-PB11_NC6-PB11") (pintype "no_connect"))
    )
    (net (code "164") (name "unconnected-(U$1-PadNC7-PF5)") (class "Default")
      (node (ref "U$1") (pin "NC7-PF5") (pinfunction "NC7-PF5_NC7-PF5") (pintype "bidirectional"))
    )
    (net (code "165") (name "unconnected-(U$1-PadNC8-PF4)") (class "Default")
      (node (ref "U$1") (pin "NC8-PF4") (pinfunction "NC8-PF4_NC8-PF4") (pintype "bidirectional"))
    )
    (net (code "166") (name "unconnected-(U$1-PadNRESET)") (class "Default")
      (node (ref "U$1") (pin "NRESET") (pinfunction "NRESET_NRESET") (pintype "input"))
    )
    (net (code "167") (name "unconnected-(U$1-PadPA1)") (class "Default")
      (node (ref "U$1") (pin "PA1") (pinfunction "PA1_PA1") (pintype "bidirectional"))
    )
    (net (code "168") (name "unconnected-(U$1-PadPA2)") (class "Default")
      (node (ref "U$1") (pin "PA2") (pinfunction "PA2_PA2") (pintype "bidirectional"))
    )
    (net (code "169") (name "unconnected-(U$1-PadPA3)") (class "Default")
      (node (ref "U$1") (pin "PA3") (pinfunction "PA3_PA3") (pintype "bidirectional"))
    )
    (net (code "170") (name "unconnected-(U$1-PadPA5)") (class "Default")
      (node (ref "U$1") (pin "PA5") (pinfunction "PA5_PA5") (pintype "bidirectional"))
    )
    (net (code "171") (name "unconnected-(U$1-PadPA7)") (class "Default")
      (node (ref "U$1") (pin "PA7") (pinfunction "PA7_PA7") (pintype "bidirectional"))
    )
    (net (code "172") (name "unconnected-(U$1-PadPA9)") (class "Default")
      (node (ref "U$1") (pin "PA9") (pinfunction "PA9_PA9") (pintype "bidirectional"))
    )
    (net (code "173") (name "unconnected-(U$1-PadPA10)") (class "Default")
      (node (ref "U$1") (pin "PA10") (pinfunction "PA10_PA10") (pintype "bidirectional"))
    )
    (net (code "174") (name "unconnected-(U$1-PadPA11)") (class "Default")
      (node (ref "U$1") (pin "PA11") (pinfunction "PA11_PA11") (pintype "bidirectional"))
    )
    (net (code "175") (name "unconnected-(U$1-PadPA12)") (class "Default")
      (node (ref "U$1") (pin "PA12") (pinfunction "PA12_PA12") (pintype "bidirectional"))
    )
    (net (code "176") (name "unconnected-(U$1-PadPA13)") (class "Default")
      (node (ref "U$1") (pin "PA13") (pinfunction "PA13_PA13") (pintype "bidirectional"))
    )
    (net (code "177") (name "unconnected-(U$1-PadPA14)") (class "Default")
      (node (ref "U$1") (pin "PA14") (pinfunction "PA14_PA14") (pintype "bidirectional"))
    )
    (net (code "178") (name "unconnected-(U$1-PadPB0)") (class "Default")
      (node (ref "U$1") (pin "PB0") (pinfunction "PB0_PB0") (pintype "bidirectional"))
    )
    (net (code "179") (name "unconnected-(U$1-PadPB13)") (class "Default")
      (node (ref "U$1") (pin "PB13") (pinfunction "PB13_PB13") (pintype "bidirectional"))
    )
    (net (code "180") (name "unconnected-(U$1-PadPC1)") (class "Default")
      (node (ref "U$1") (pin "PC1") (pinfunction "PC1_PC1") (pintype "bidirectional"))
    )
    (net (code "181") (name "unconnected-(U$1-PadPC4)") (class "Default")
      (node (ref "U$1") (pin "PC4") (pinfunction "PC4_PC4") (pintype "bidirectional"))
    )
    (net (code "182") (name "unconnected-(U$1-PadPC5)") (class "Default")
      (node (ref "U$1") (pin "PC5") (pinfunction "PC5_PC5") (pintype "bidirectional"))
    )
    (net (code "183") (name "unconnected-(U$1-PadPC13)") (class "Default")
      (node (ref "U$1") (pin "PC13") (pinfunction "PC13_PC13") (pintype "bidirectional"))
    )
    (net (code "184") (name "unconnected-(U$1-PadPC14)") (class "Default")
      (node (ref "U$1") (pin "PC14") (pinfunction "PC14_PC14") (pintype "bidirectional"))
    )
    (net (code "185") (name "unconnected-(U$1-PadPC15)") (class "Default")
      (node (ref "U$1") (pin "PC15") (pinfunction "PC15_PC15") (pintype "bidirectional"))
    )
    (net (code "186") (name "unconnected-(U$1-PadPF0-PH0)") (class "Default")
      (node (ref "U$1") (pin "PF0-PH0") (pinfunction "PF0-PH0_PF0-PH0") (pintype "bidirectional"))
    )
  )
)
